# 1-Schematic_8_Bit_Computer_-_Through_Hol.net
KiCad netlist of a schematic drawn in EasyEDA
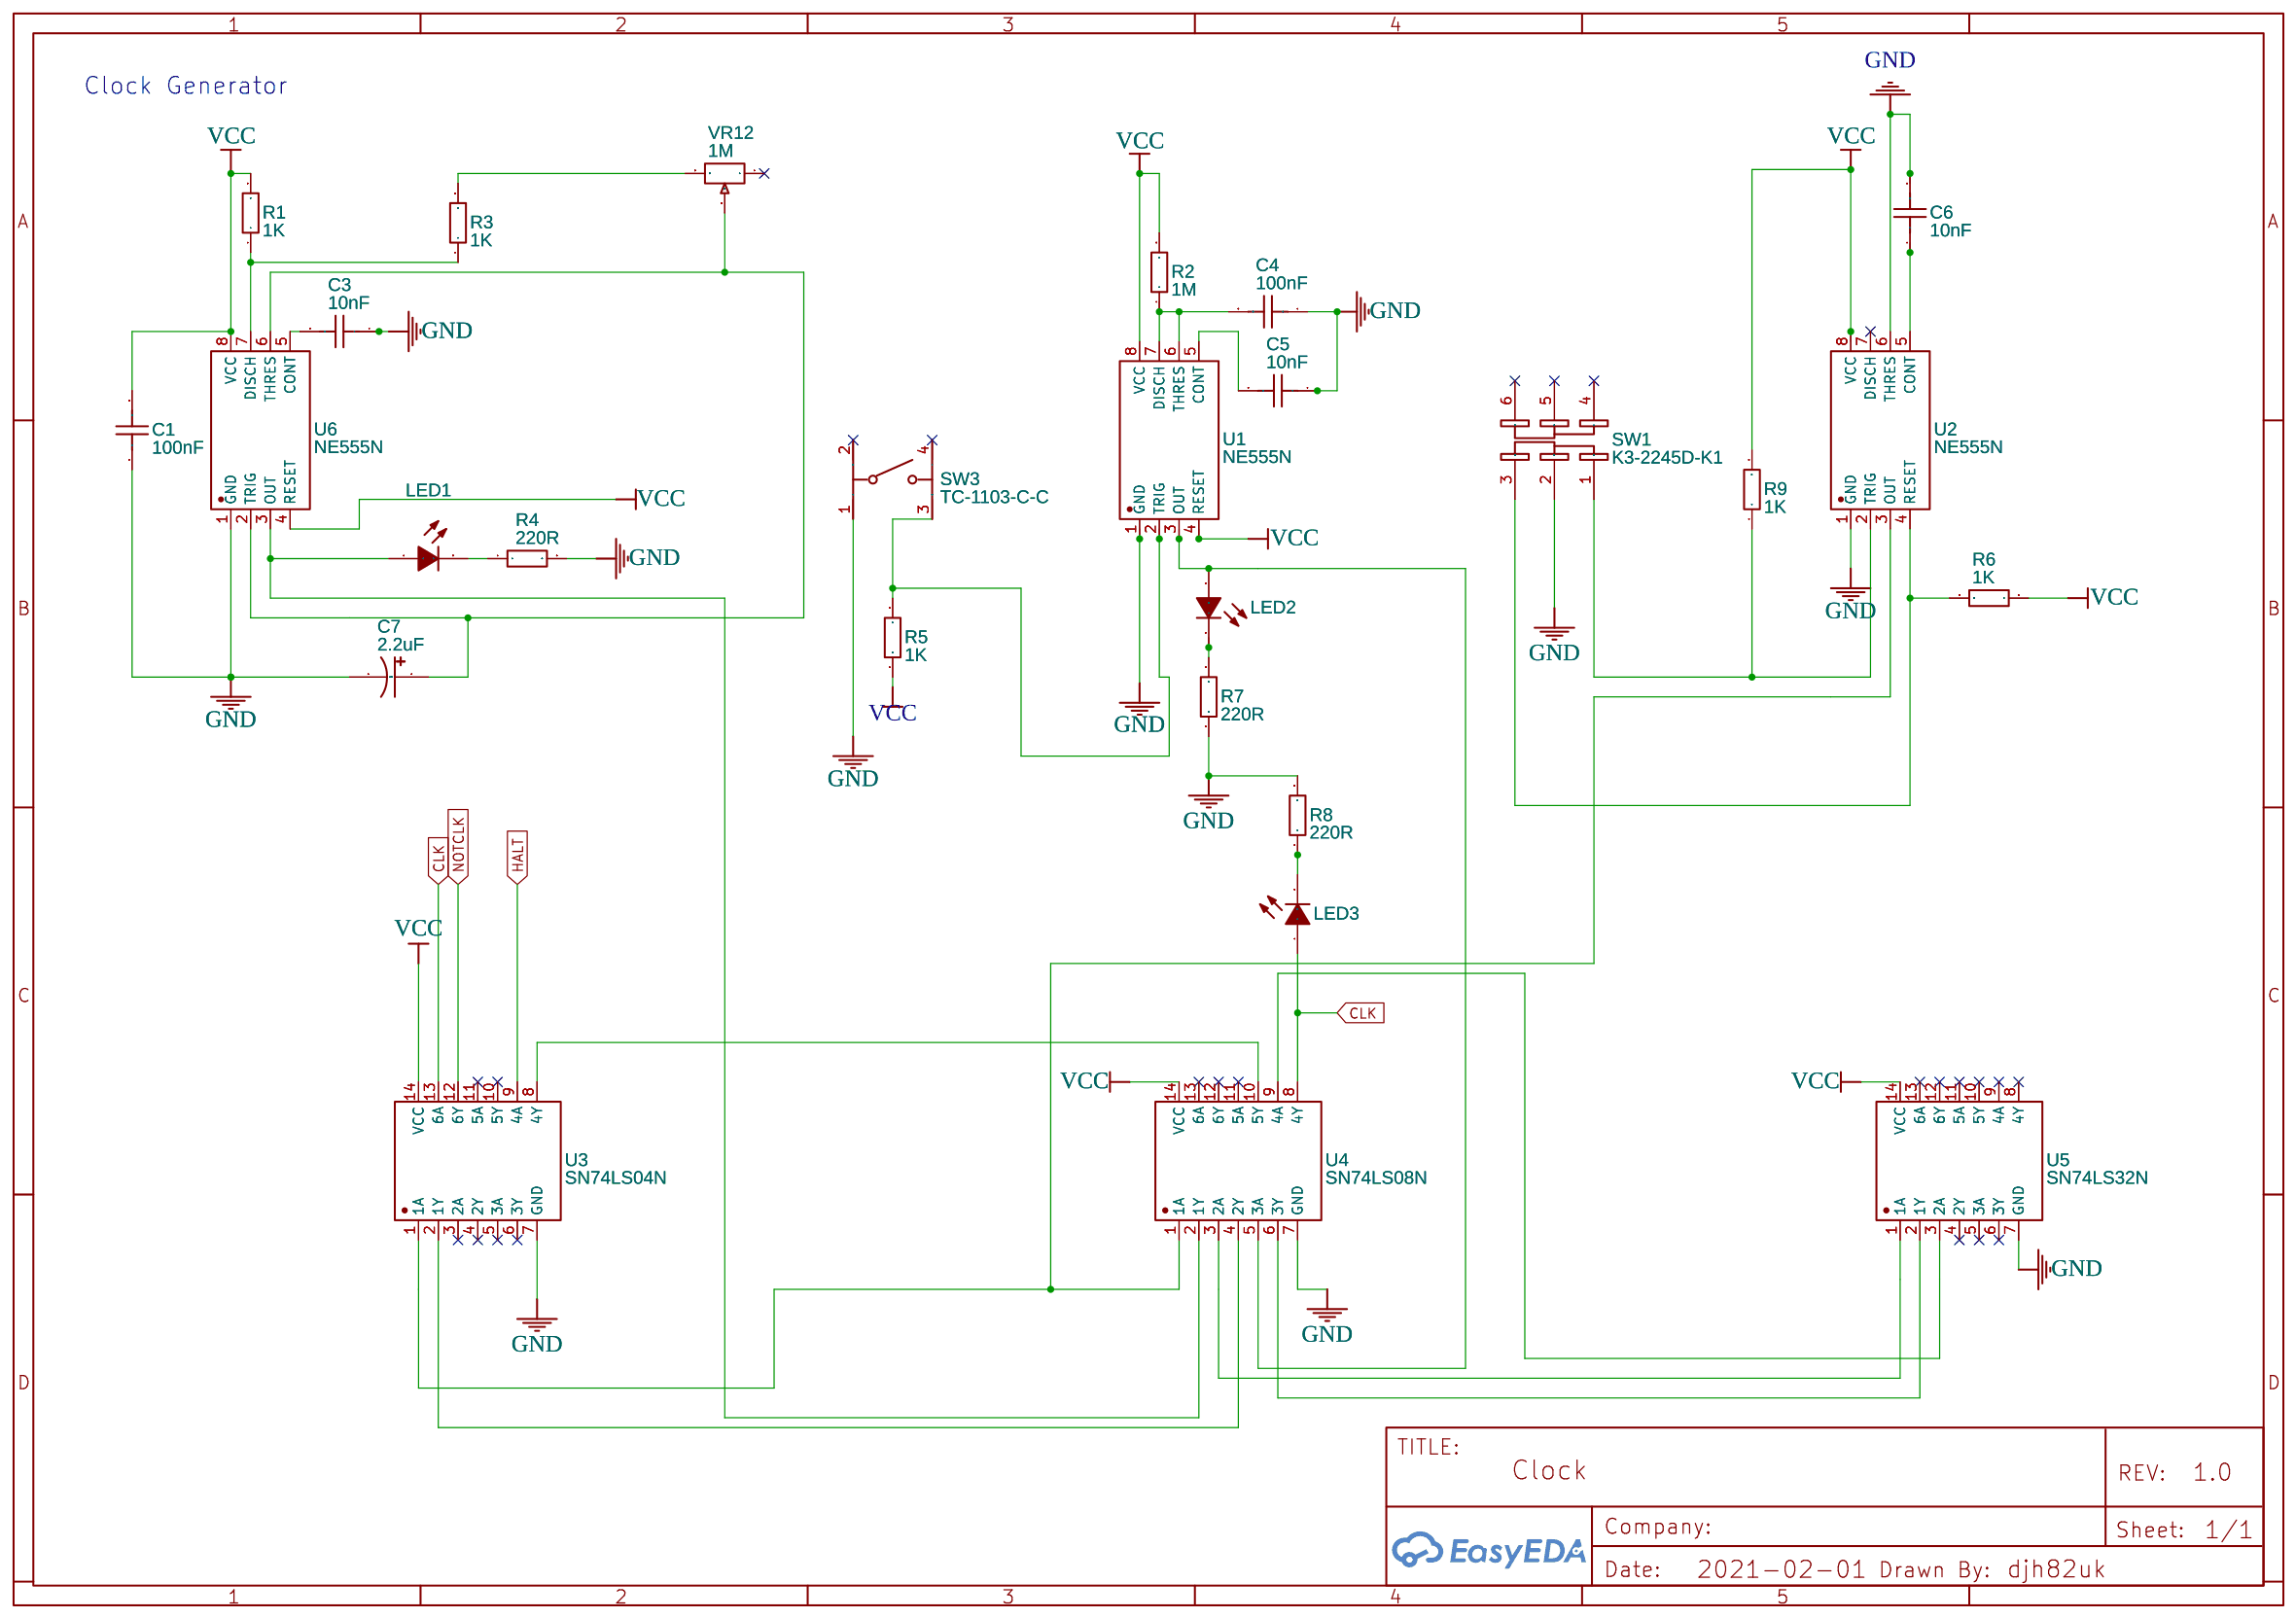
[diagram p0: Clock Circuit]
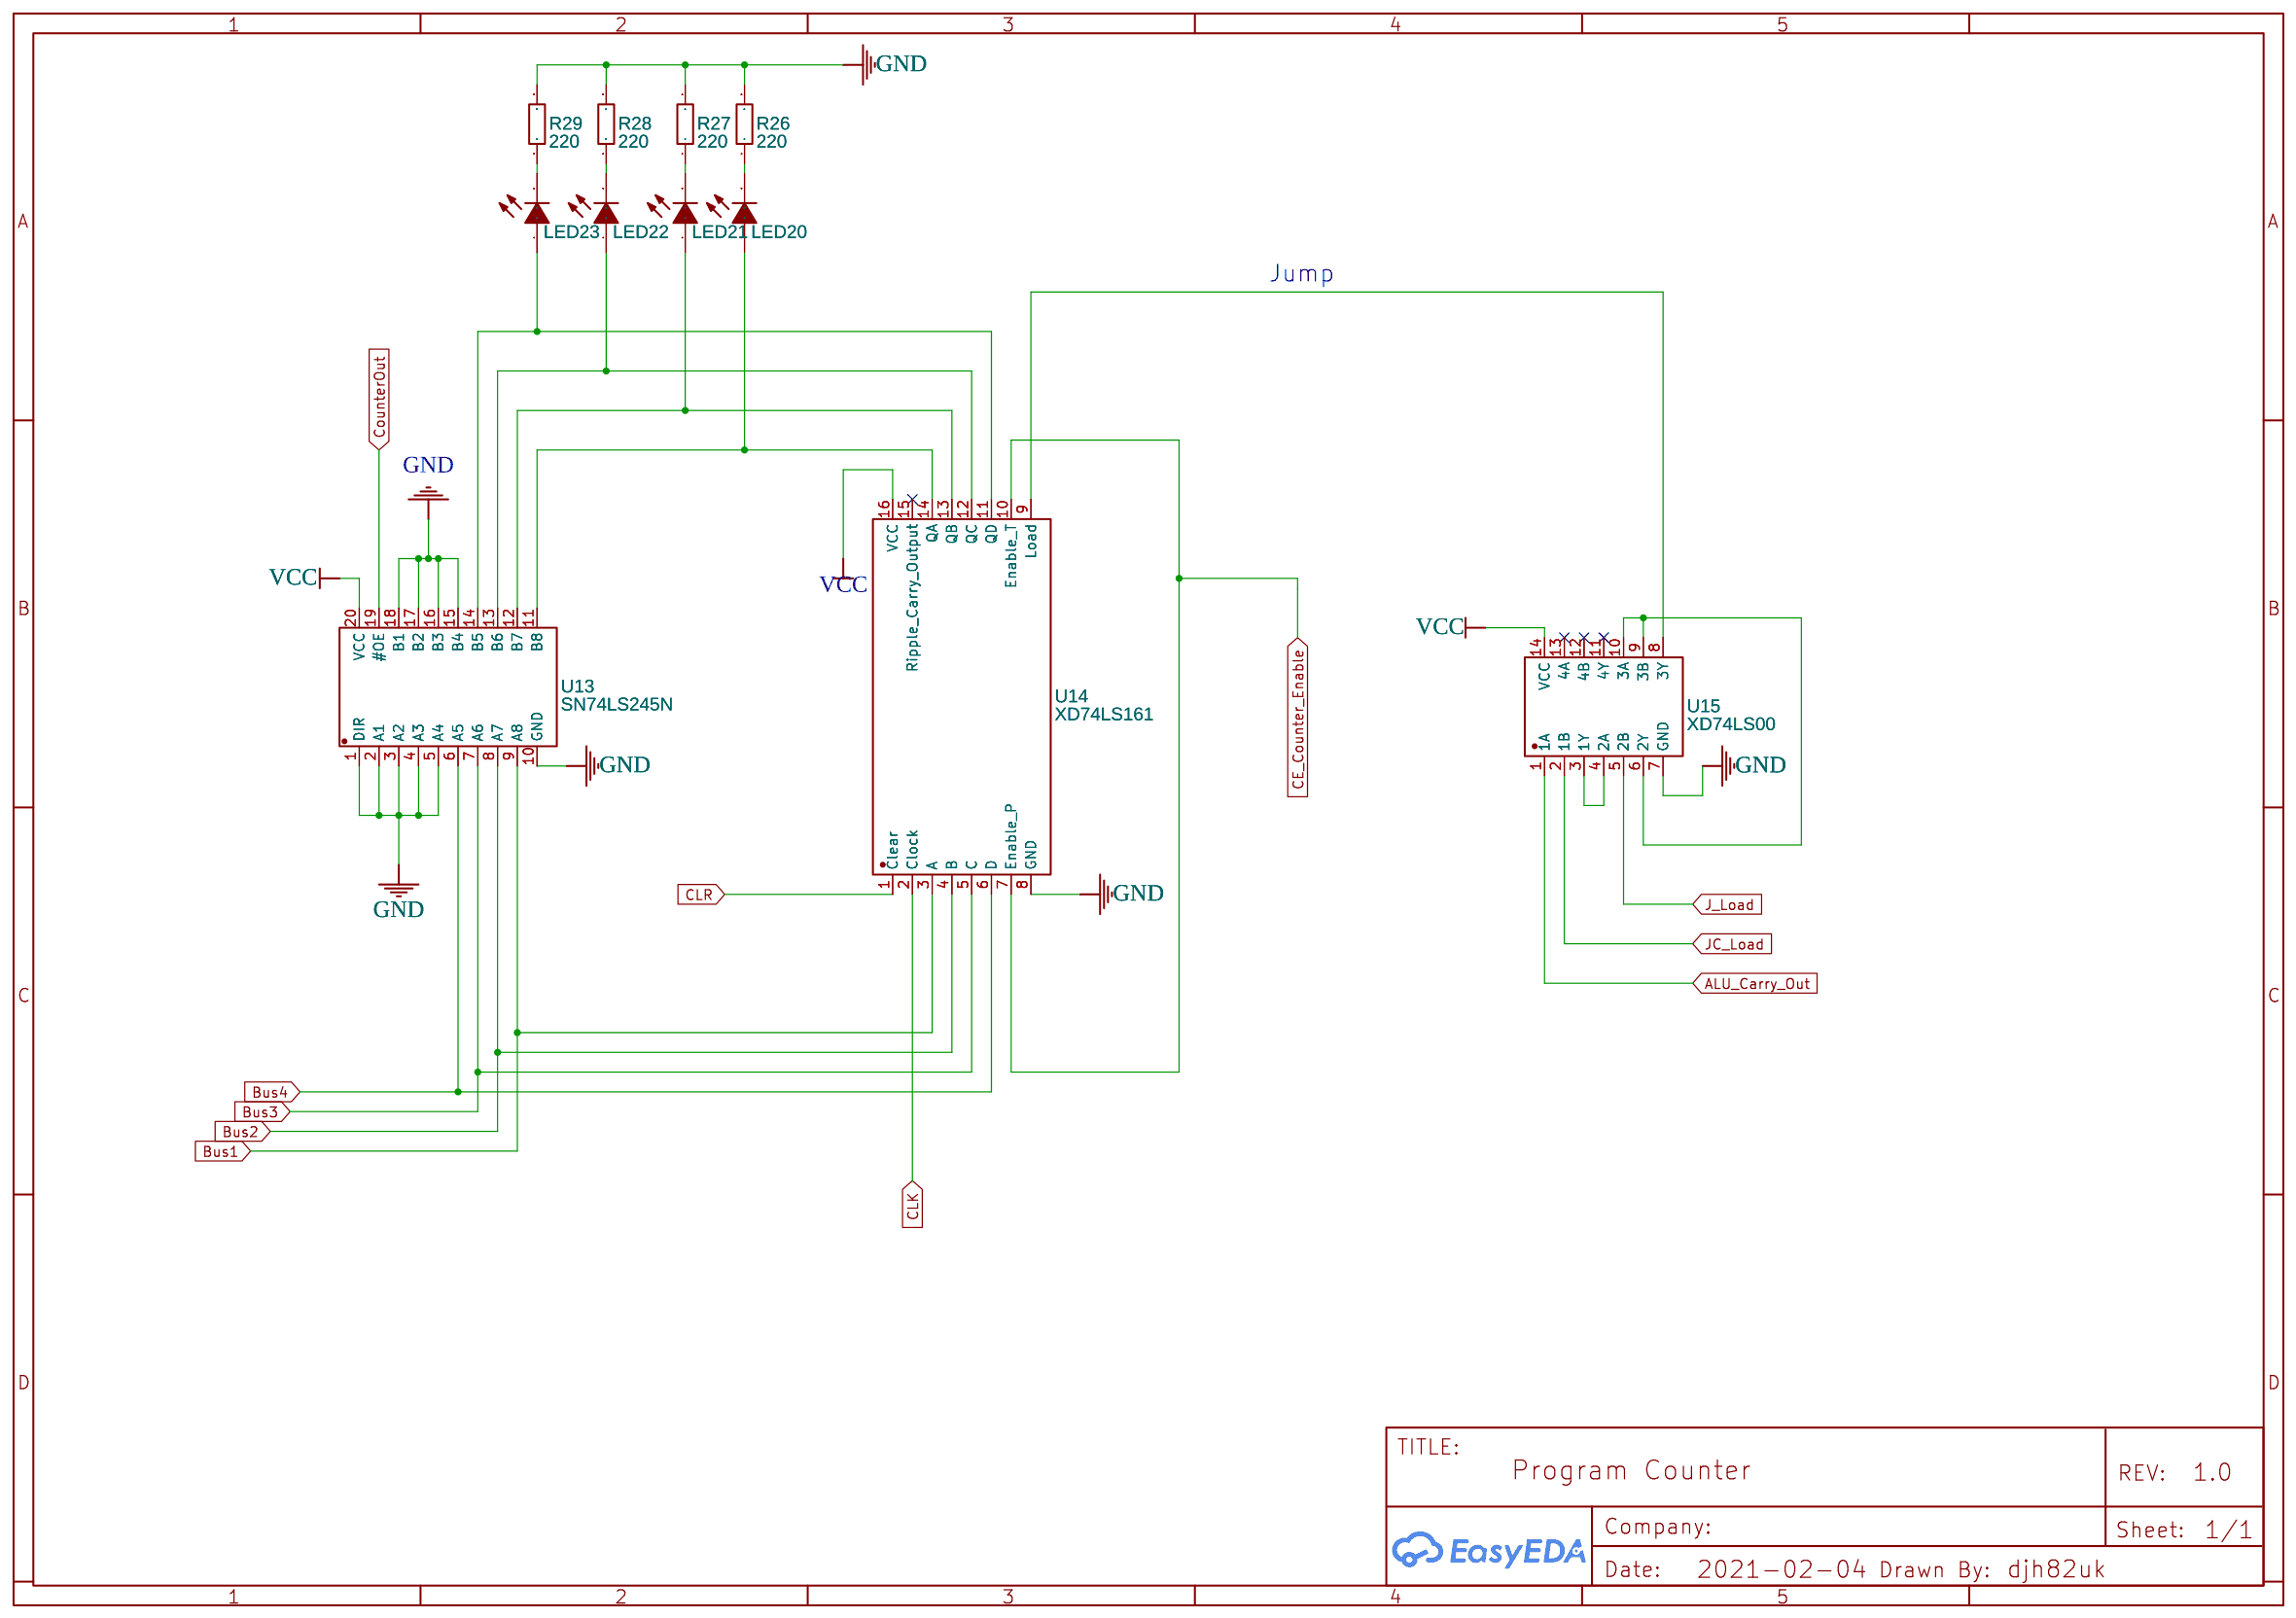
[diagram p1: Program Counter]
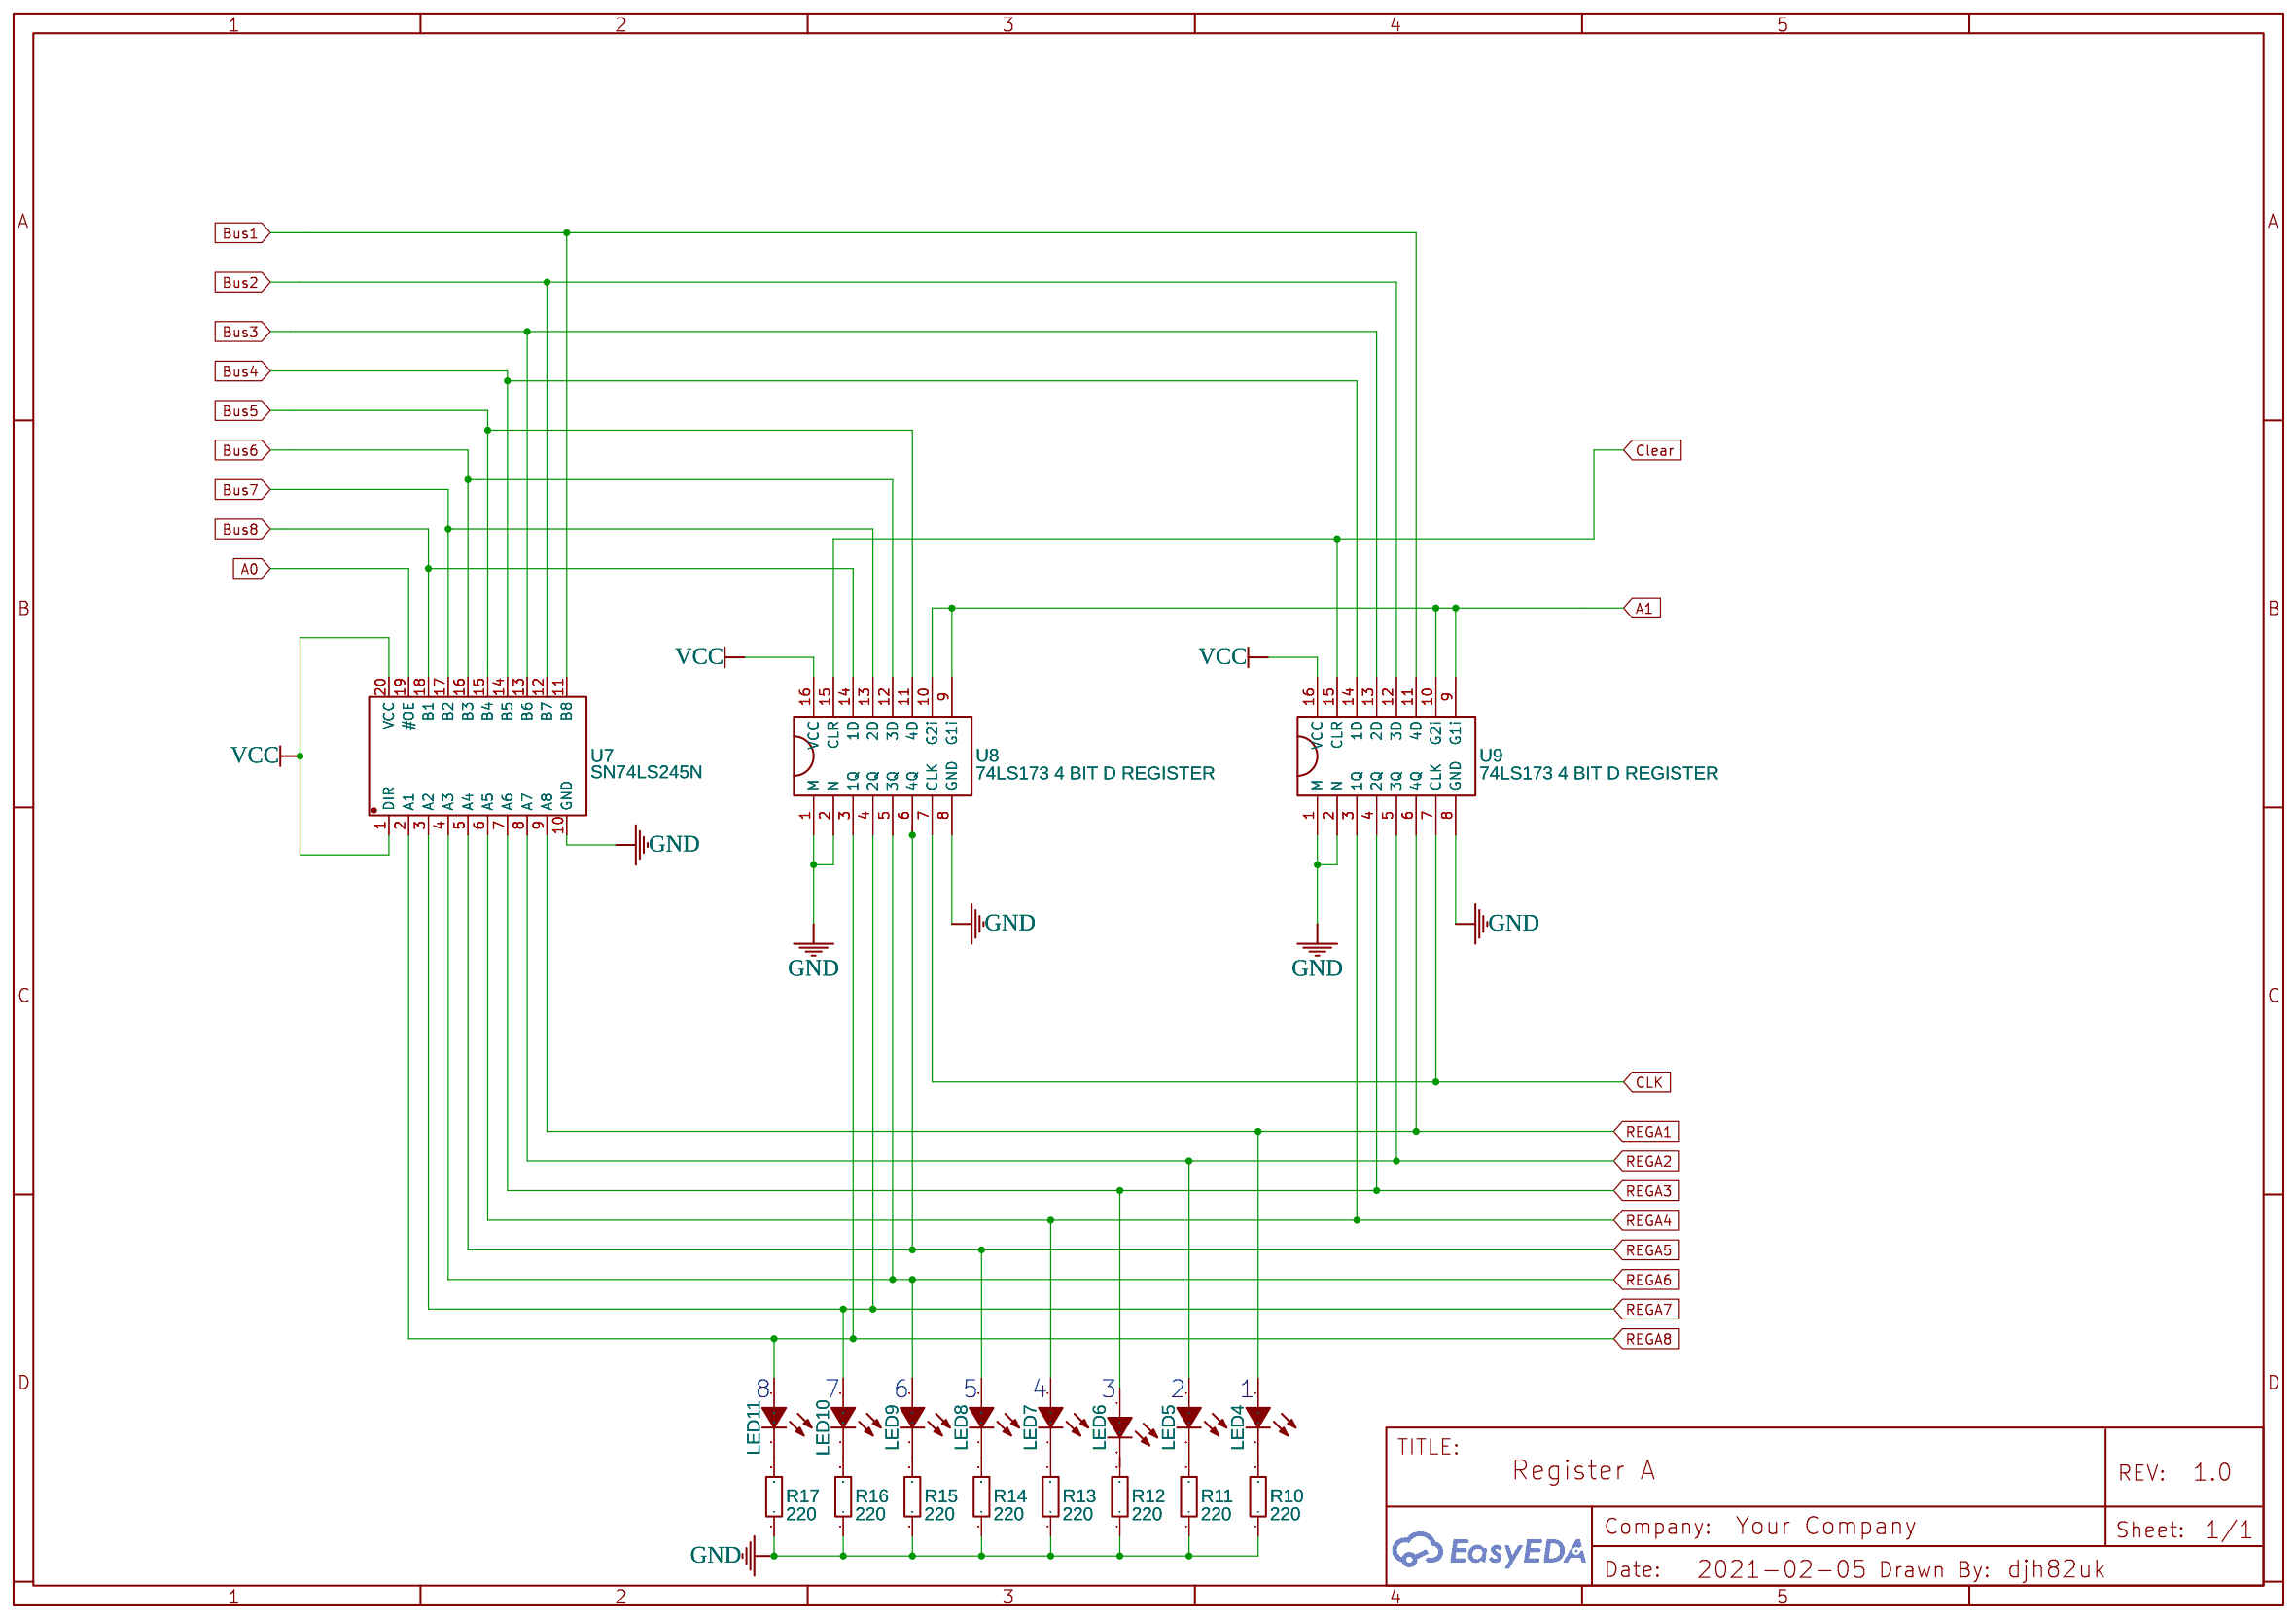
[diagram p2: Register A]
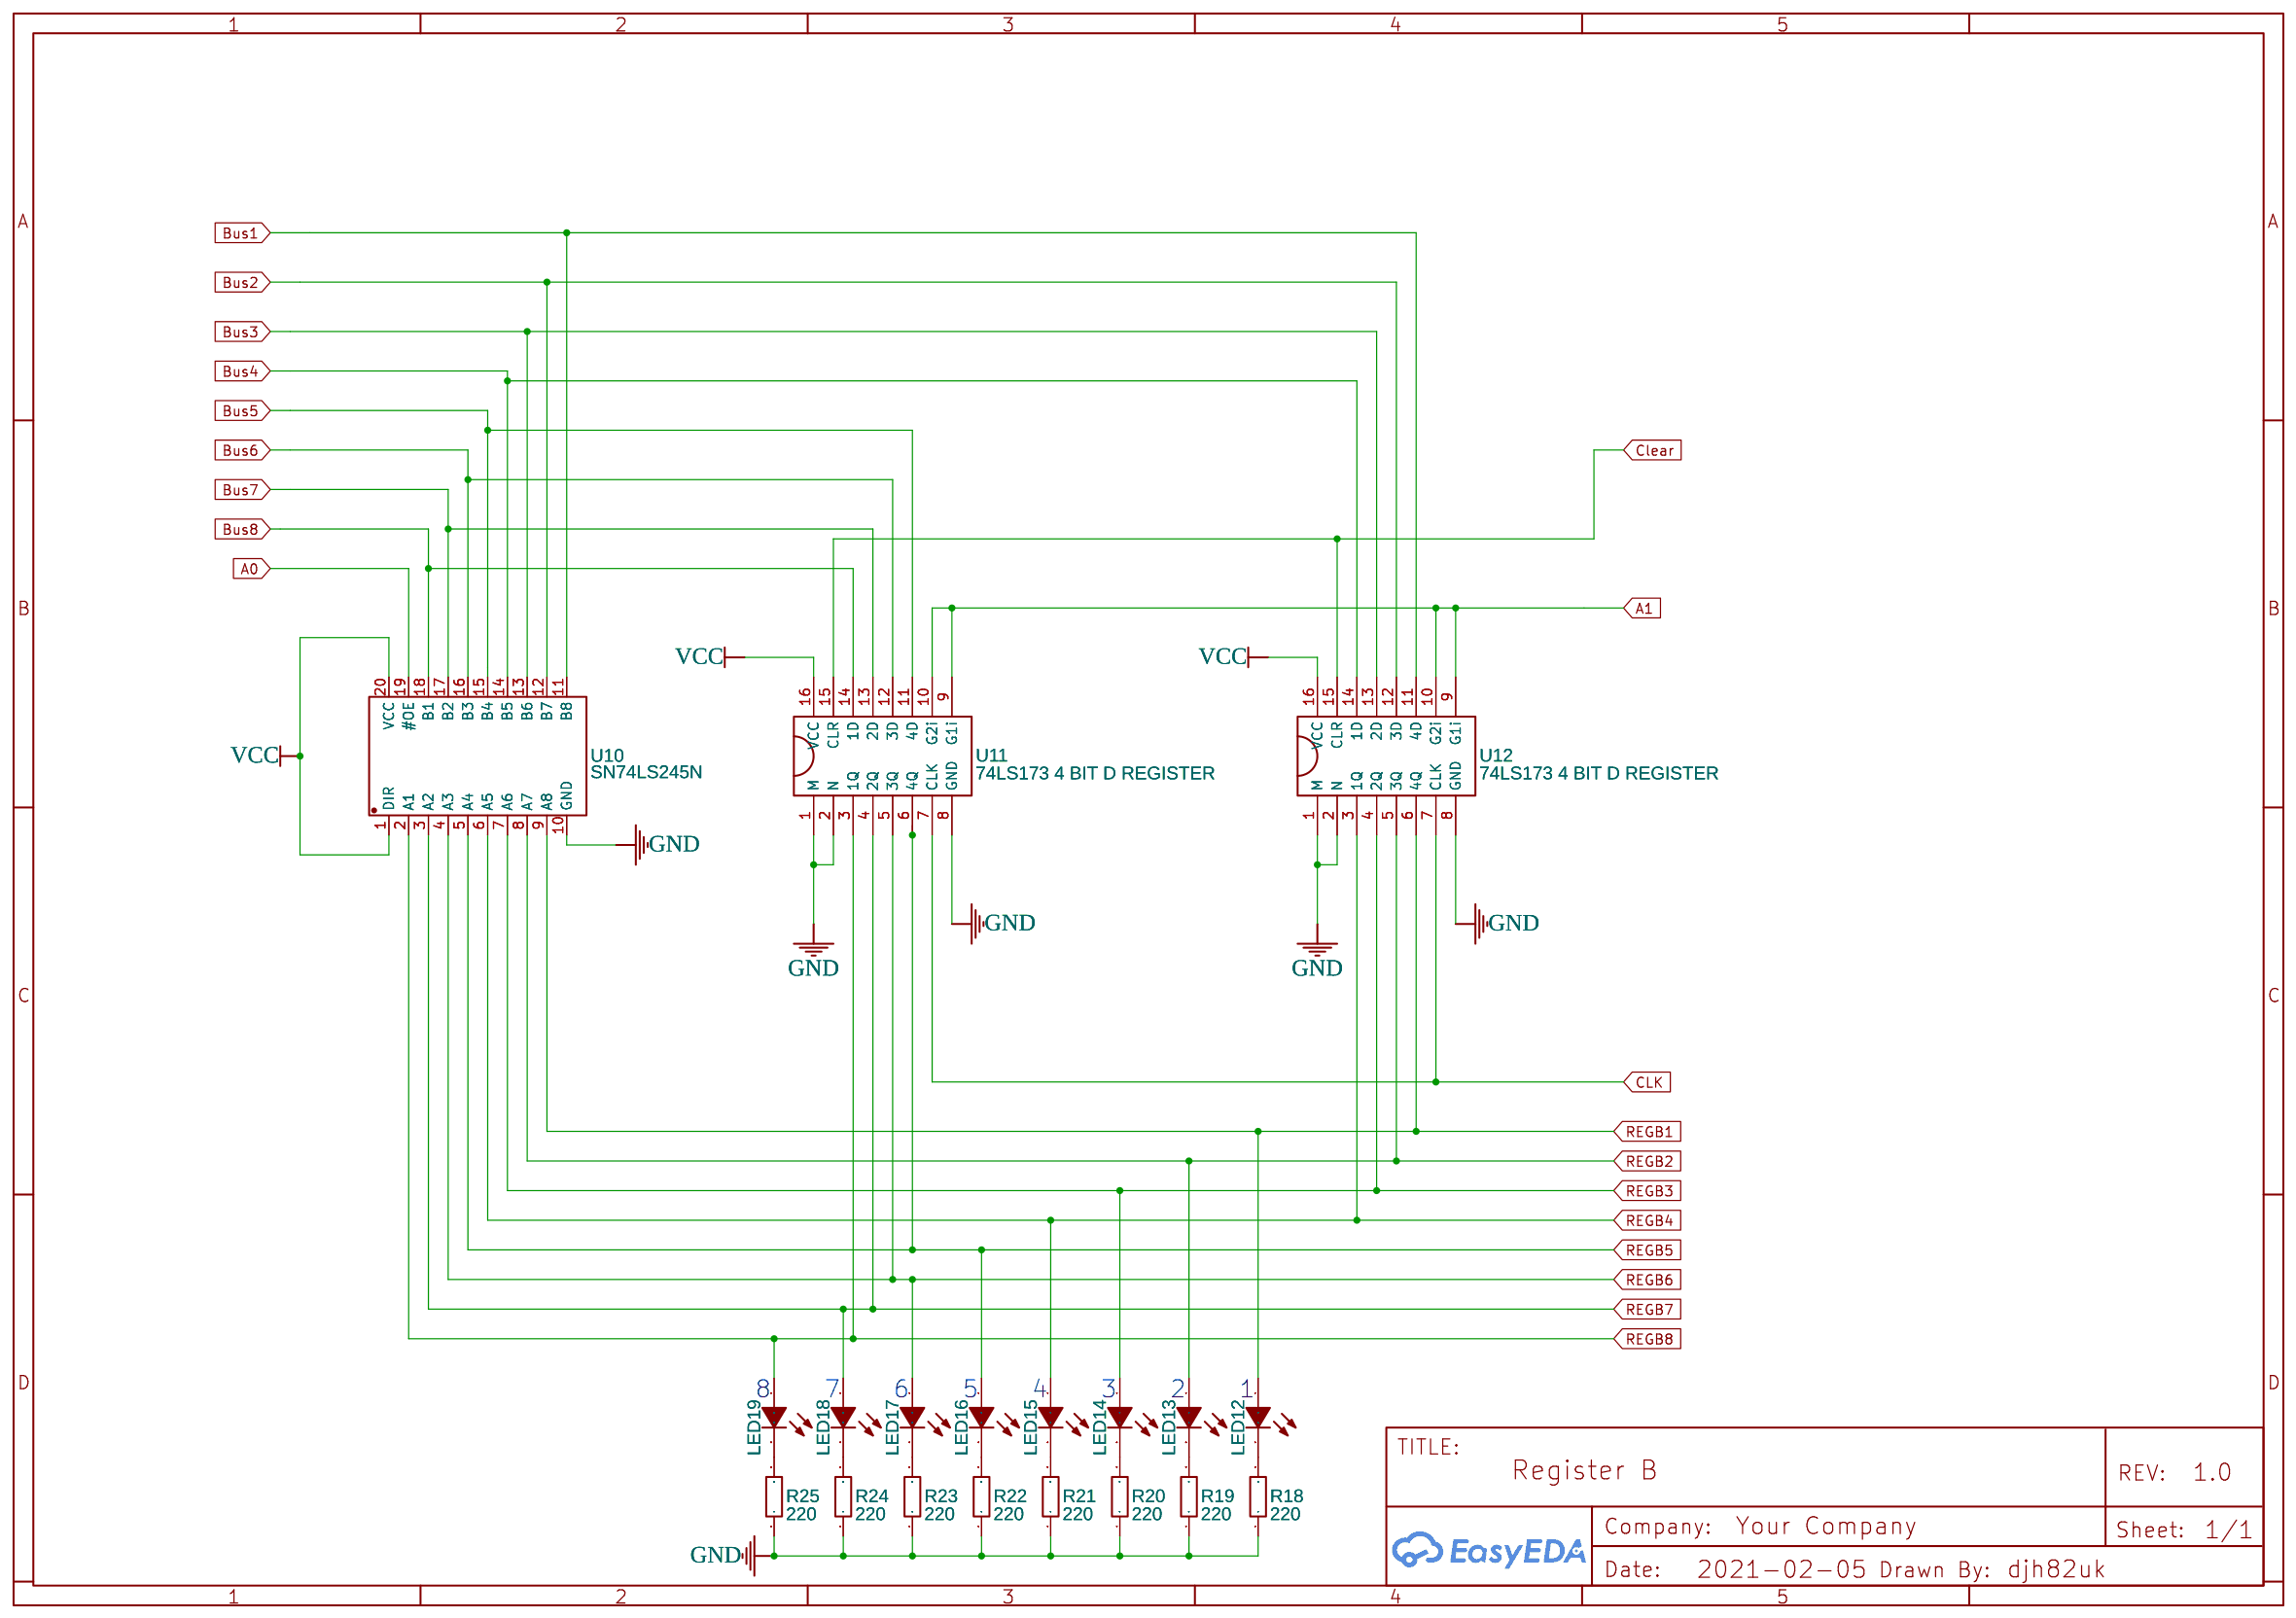
[diagram p3: Register B]
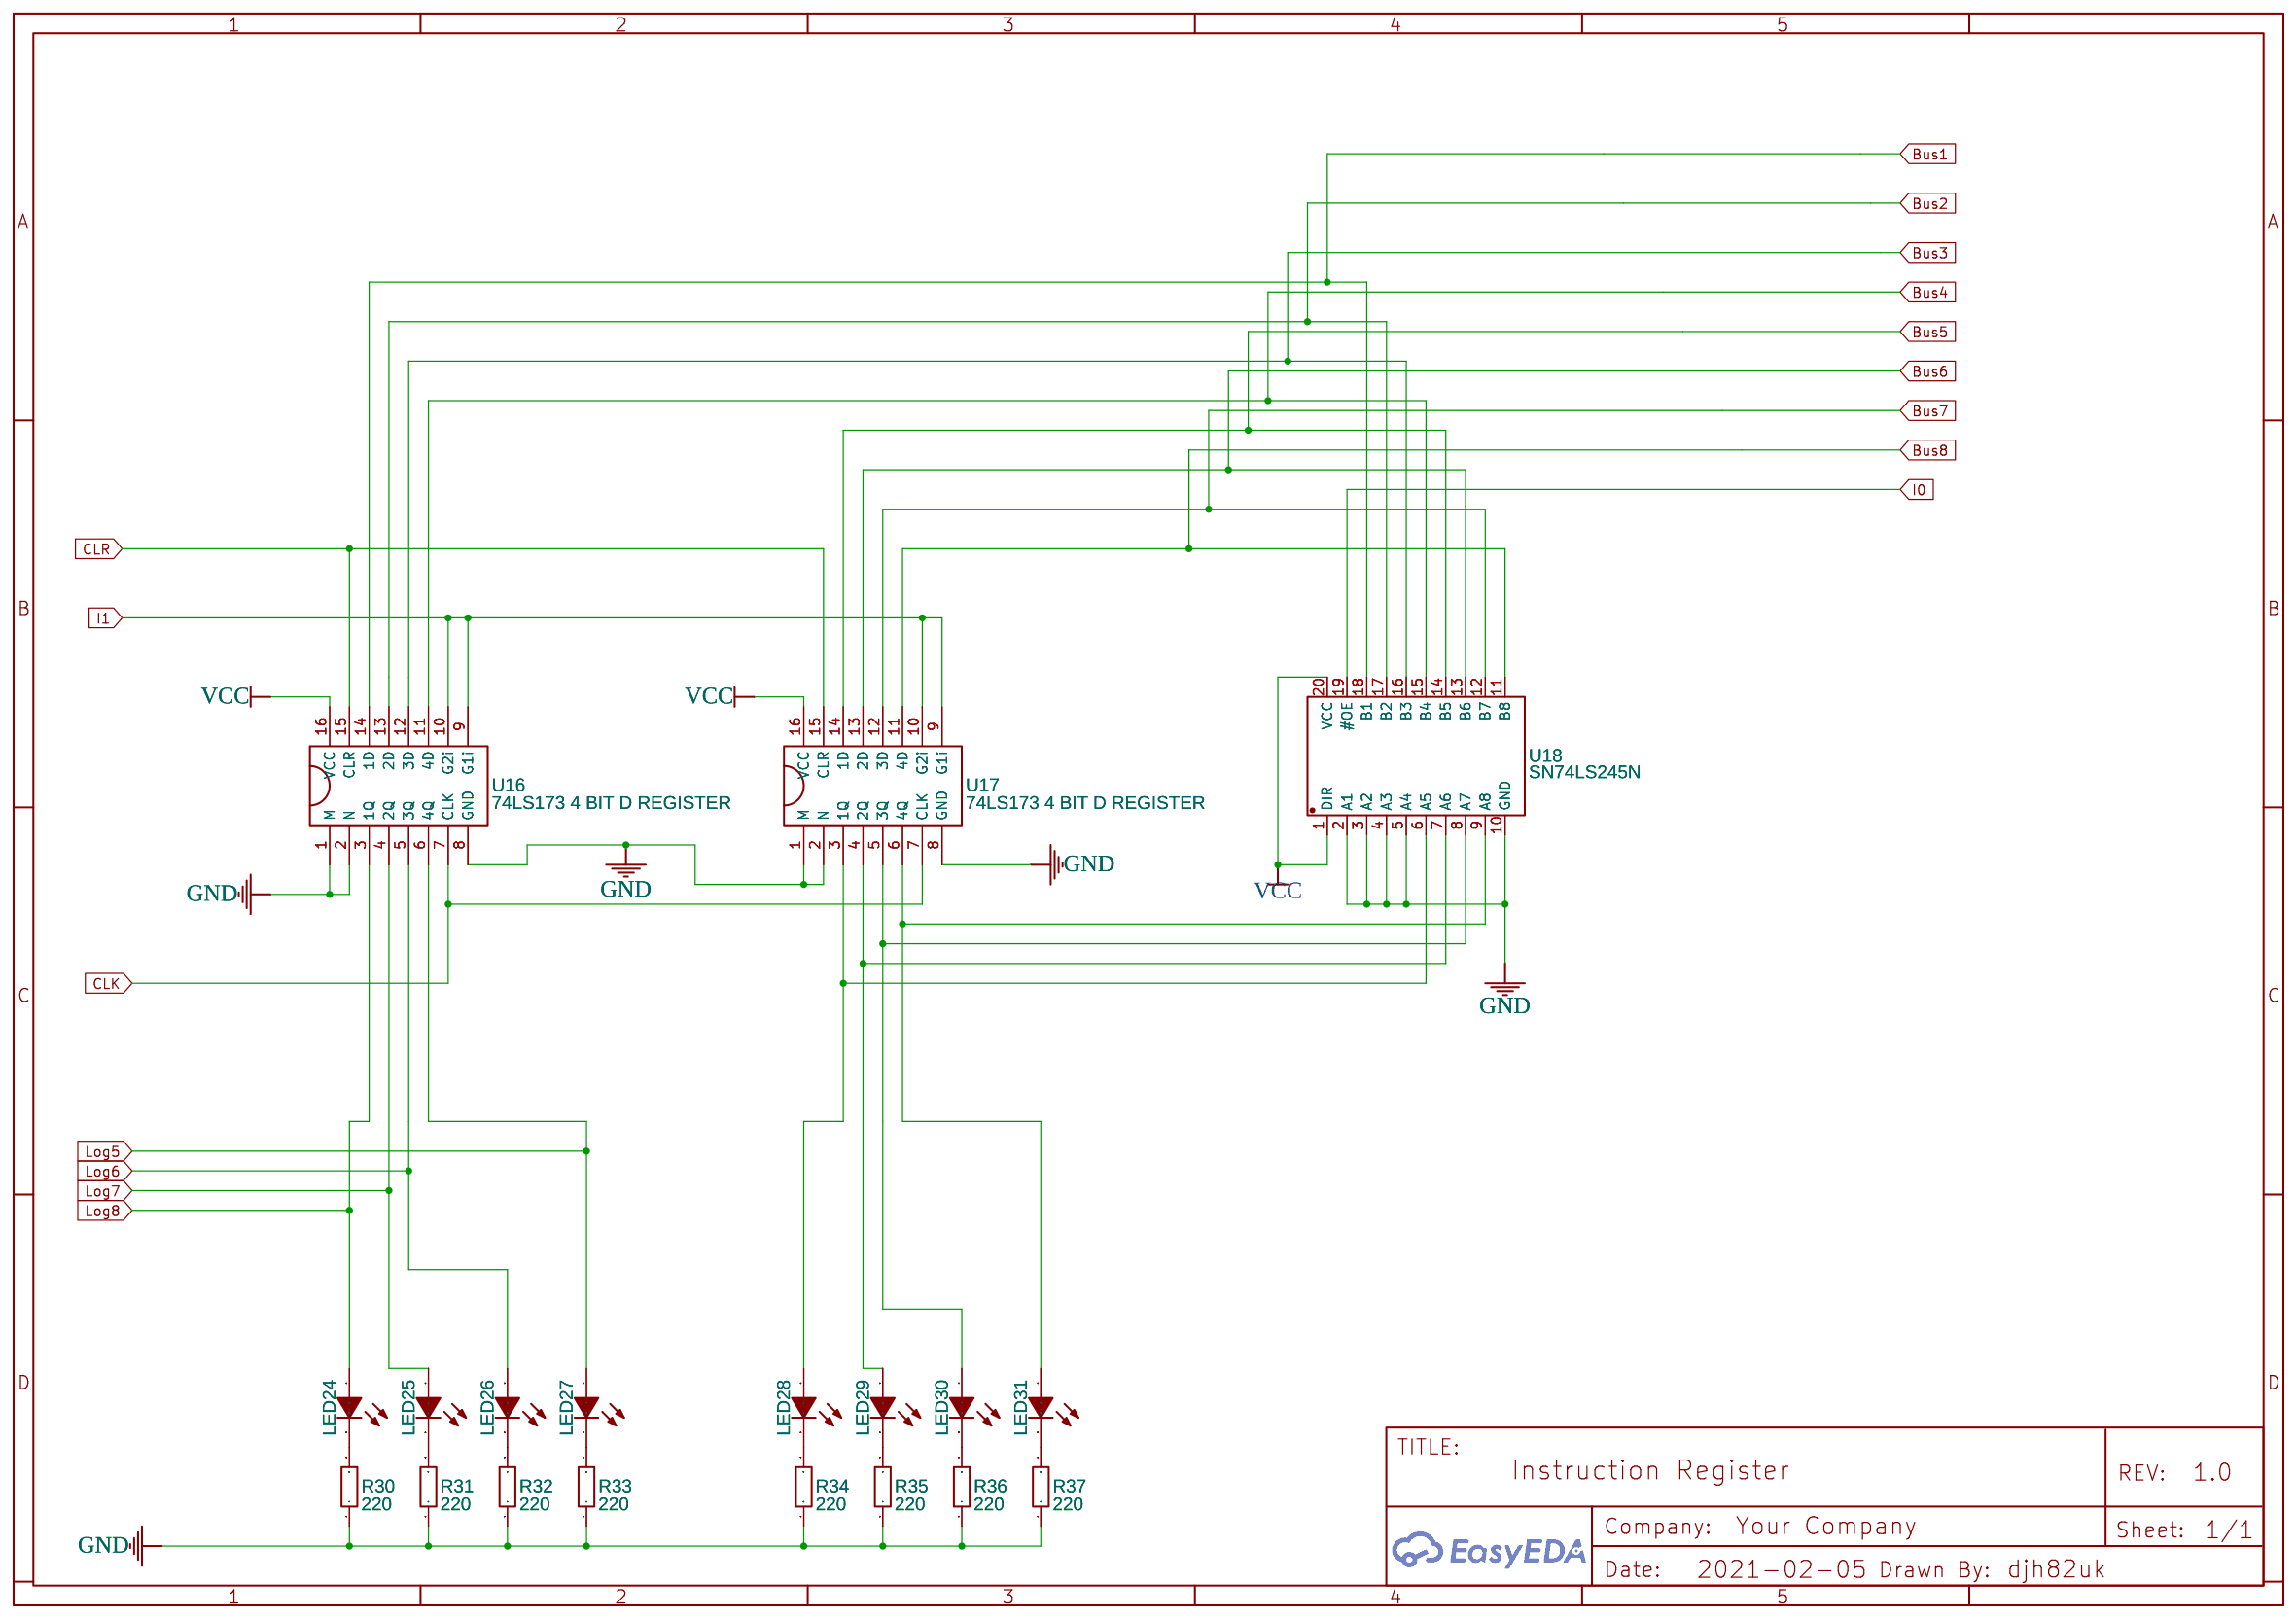
[diagram p4: Instruction Register]
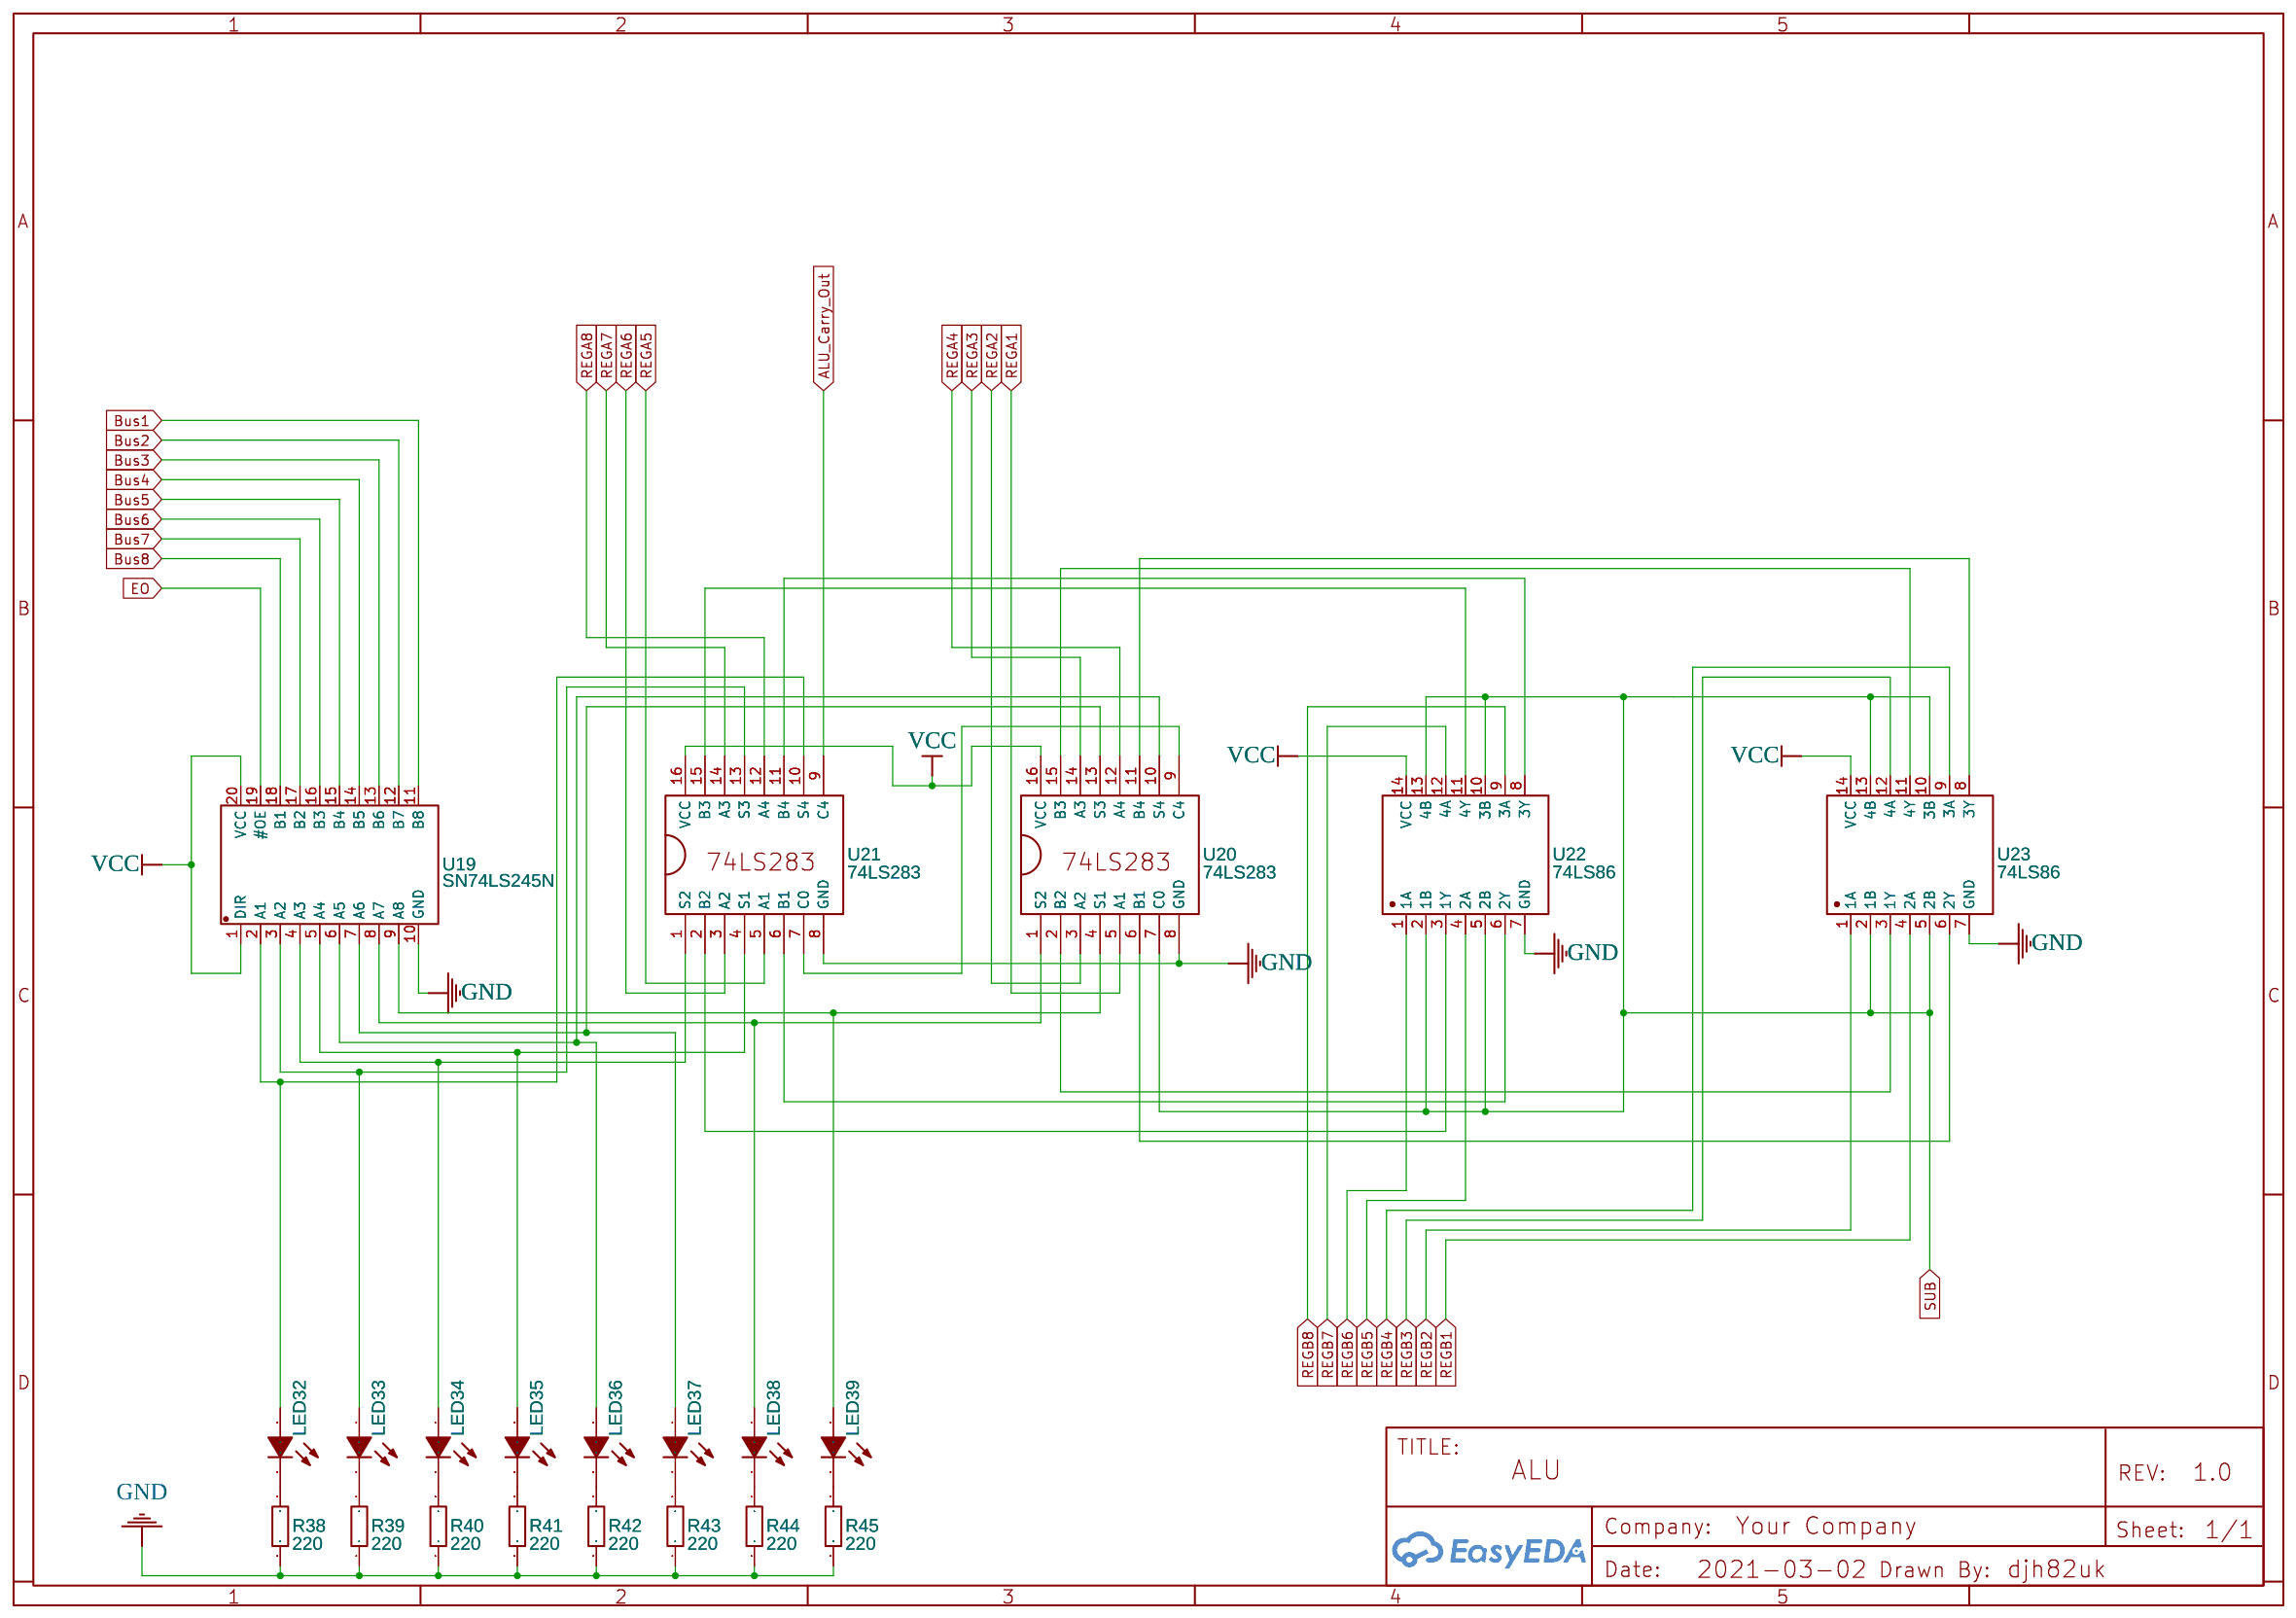
[diagram p5: ALU]
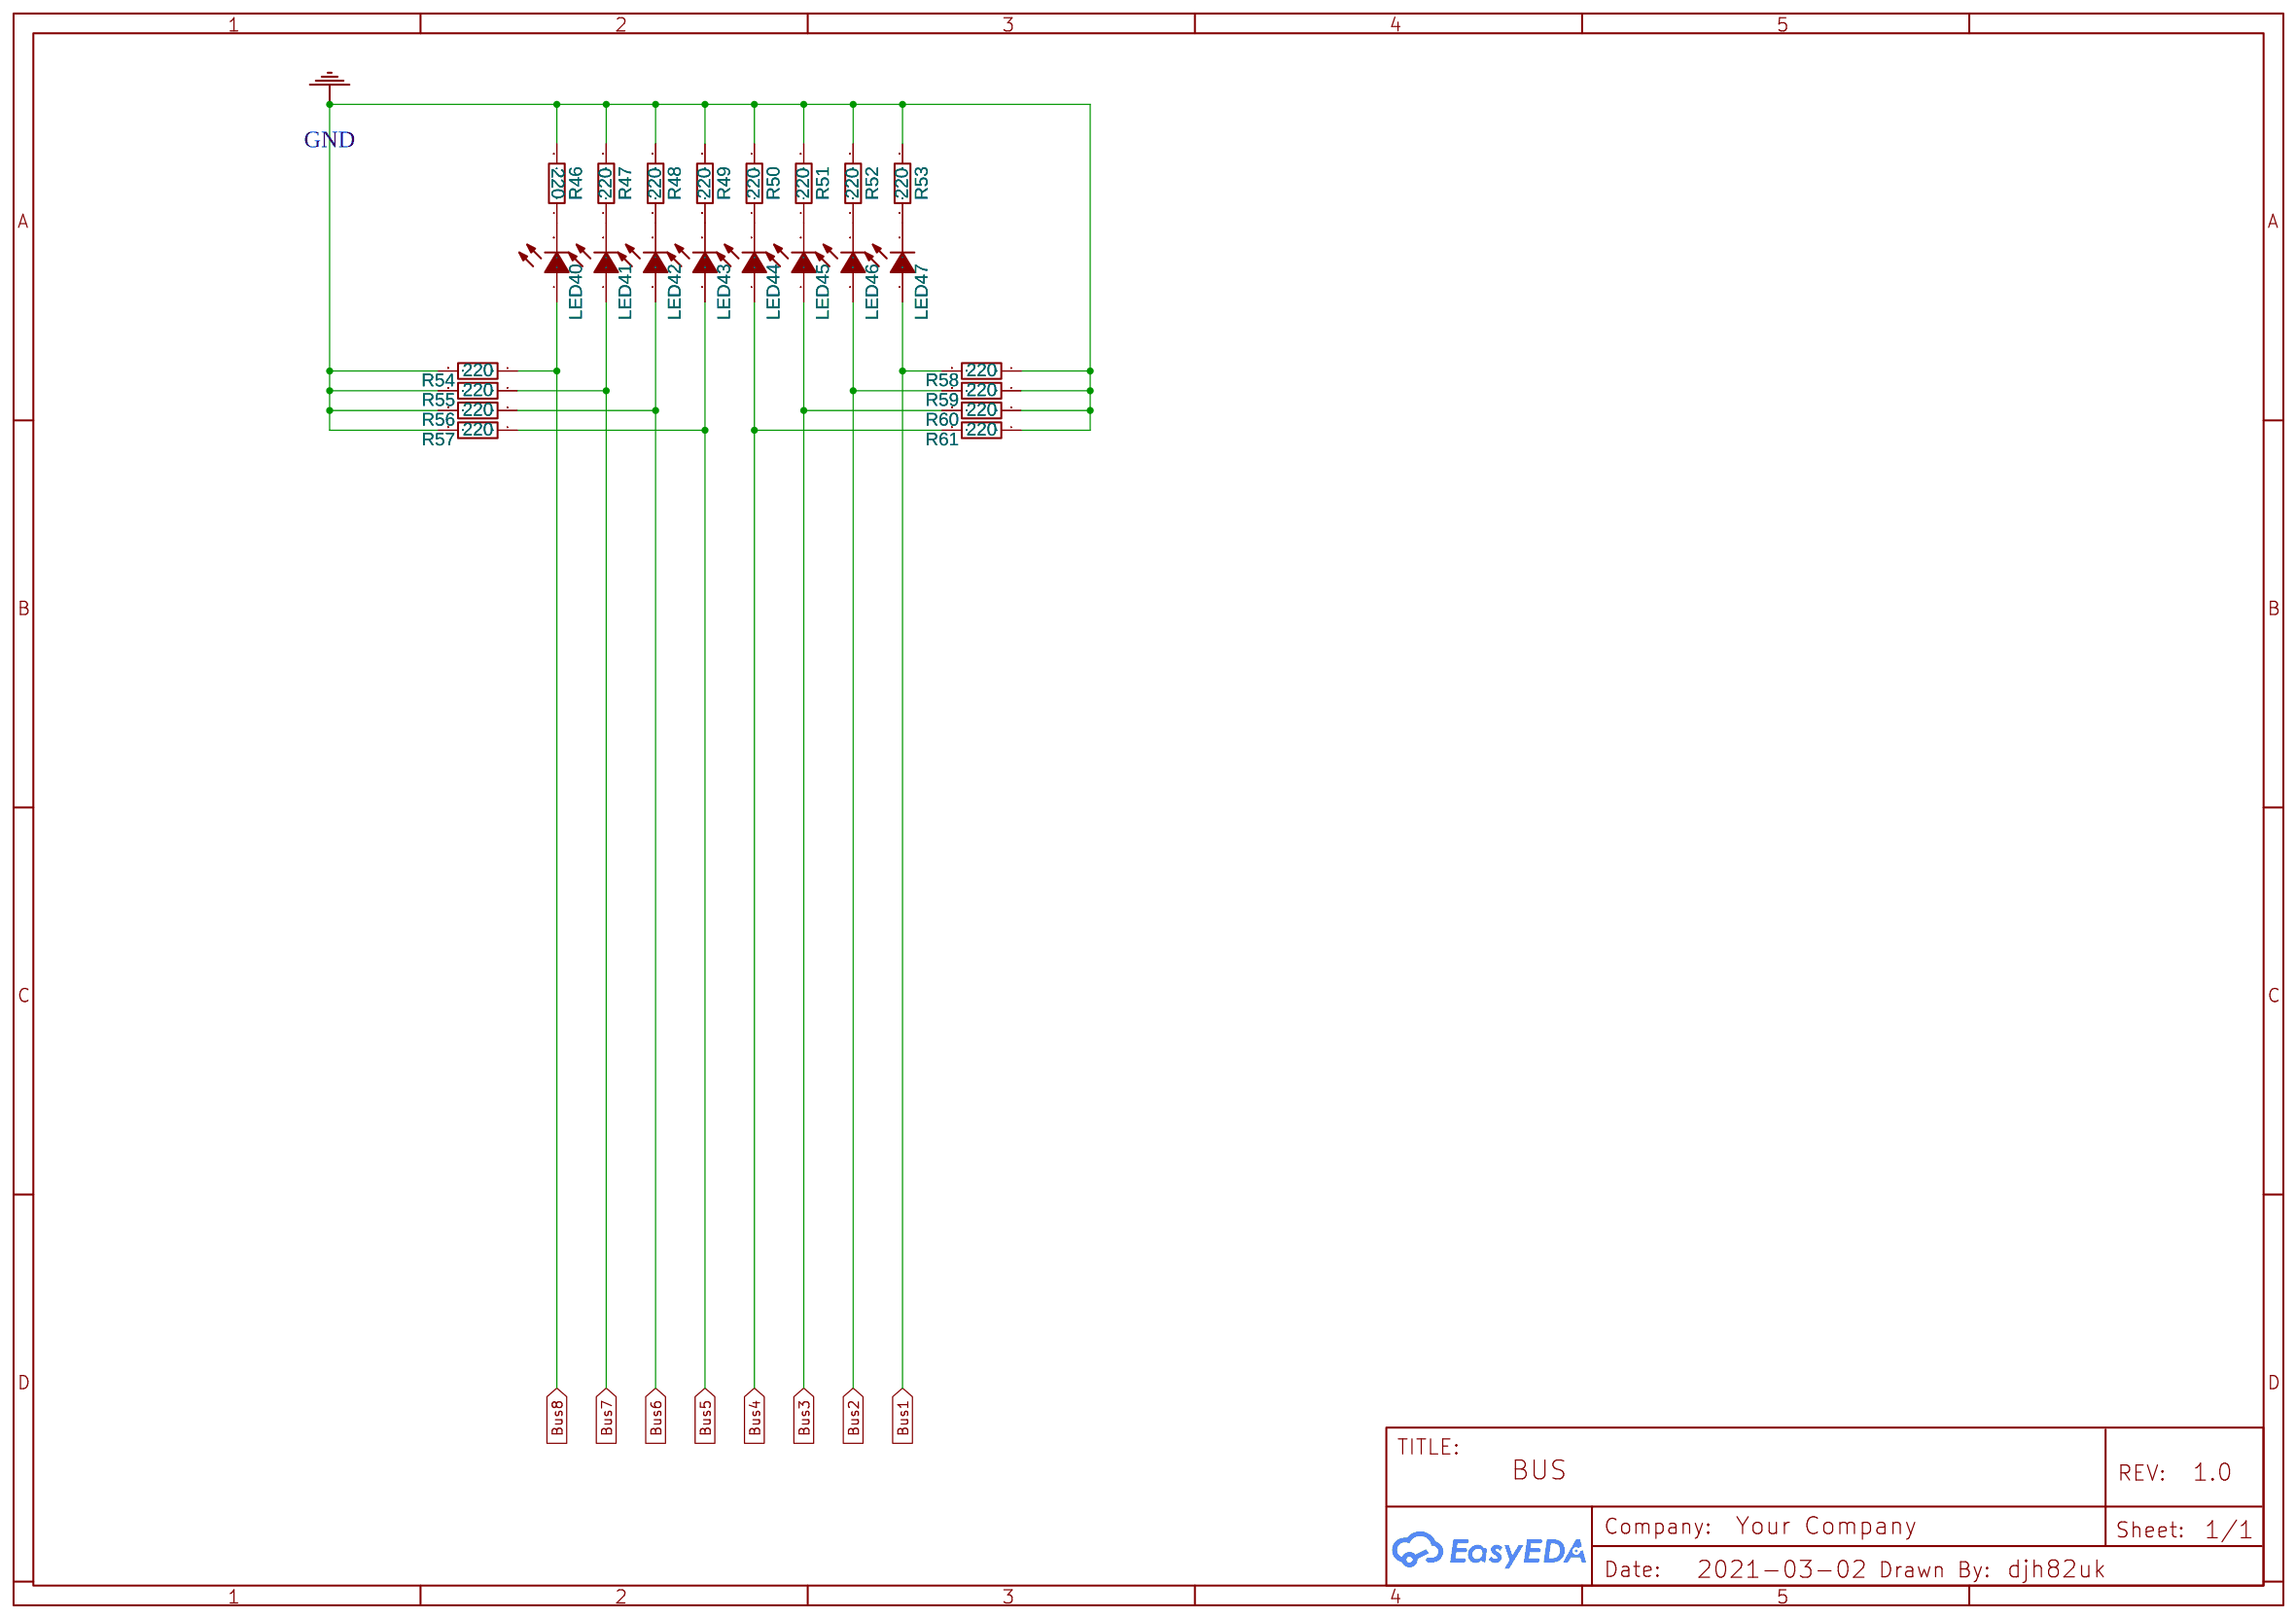
[diagram p6: BUS]

(export (version "E")
  (design (tool "Eeschema 10.0.6"))
  (components
    (comp (ref "C1")
      (value "100nF")
      (fields
        (field (name "BOM_Manufacturer Part") "CC1H103ZC4PD3F4D30MF")
        (field (name "BOM_Supplier Part") "C254066")
      )
      (libsource (lib "") (part "CC1H103ZC4PD3F4D30MF"))
    )
    (comp (ref "C3")
      (value "10nF")
      (fields
        (field (name "BOM_Manufacturer Part") "CC1H103ZC4PD3F4D30MF")
        (field (name "BOM_Supplier Part") "C254066")
      )
      (libsource (lib "") (part "CC1H103ZC4PD3F4D30MF_1"))
    )
    (comp (ref "C4")
      (value "100nF")
      (fields
        (field (name "BOM_Manufacturer Part") "CC1H103ZC4PD3F4D30MF")
        (field (name "BOM_Supplier Part") "C254066")
      )
      (libsource (lib "") (part "CC1H103ZC4PD3F4D30MF_1"))
    )
    (comp (ref "C5")
      (value "10nF")
      (fields
        (field (name "BOM_Manufacturer Part") "CC1H103ZC4PD3F4D30MF")
        (field (name "BOM_Supplier Part") "C254066")
      )
      (libsource (lib "") (part "CC1H103ZC4PD3F4D30MF_1"))
    )
    (comp (ref "C6")
      (value "10nF")
      (fields
        (field (name "BOM_Manufacturer Part") "CC1H103ZC4PD3F4D30MF")
        (field (name "BOM_Supplier Part") "C254066")
      )
      (libsource (lib "") (part "CC1H103ZC4PD3F4D30MF"))
    )
    (comp (ref "C7")
      (value "2.2uF")
      (fields
        (field (name "BOM_Manufacturer Part") "RGA2R2M1HSA-0511G")
        (field (name "BOM_Supplier Part") "C358629")
      )
      (libsource (lib "") (part "RGA2R2M1HSA-0511G"))
    )
    (comp (ref "LED1")
      (value "333-2SYGD/S530-E2-L")
      (fields (field (name "BOM_Supplier Part") "C99697"))
      (libsource (lib "") (part "333-2SYGD/S530-E2-L"))
    )
    (comp (ref "LED2")
      (value "333-2SYGD/S530-E2-L")
      (fields (field (name "BOM_Supplier Part") "C99697"))
      (libsource (lib "") (part "333-2SYGD/S530-E2-L_2"))
    )
    (comp (ref "LED3")
      (value "333-2SYGD/S530-E2-L")
      (fields (field (name "BOM_Supplier Part") "C99697"))
      (libsource (lib "") (part "333-2SYGD/S530-E2-L_1"))
    )
    (comp (ref "R1")
      (value "1K")
      (fields
        (field (name "BOM_Manufacturer Part") "MFR0W4F1003A50")
        (field (name "BOM_Supplier Part") "C58597")
      )
      (libsource (lib "") (part "MFR0W4F1003A50_1"))
    )
    (comp (ref "R2")
      (value "1M")
      (fields
        (field (name "BOM_Manufacturer Part") "MFR0W4F1003A50")
        (field (name "BOM_Supplier Part") "C58597")
      )
      (libsource (lib "") (part "MFR0W4F1003A50_1"))
    )
    (comp (ref "R3")
      (value "1K")
      (fields
        (field (name "BOM_Manufacturer Part") "MFR0W4F1003A50")
        (field (name "BOM_Supplier Part") "C58597")
      )
      (libsource (lib "") (part "MFR0W4F1003A50_1"))
    )
    (comp (ref "R4")
      (value "220R")
      (fields
        (field (name "BOM_Manufacturer Part") "MFR0W4F1003A50")
        (field (name "BOM_Supplier Part") "C58597")
      )
      (libsource (lib "") (part "MFR0W4F1003A50_2"))
    )
    (comp (ref "R5")
      (value "1K")
      (fields
        (field (name "BOM_Manufacturer Part") "MFR0W4F1003A50")
        (field (name "BOM_Supplier Part") "C58597")
      )
      (libsource (lib "") (part "MFR0W4F1003A50_1"))
    )
    (comp (ref "R6")
      (value "1K")
      (fields
        (field (name "BOM_Manufacturer Part") "MFR0W4F1003A50")
        (field (name "BOM_Supplier Part") "C58597")
      )
      (libsource (lib "") (part "MFR0W4F1003A50"))
    )
    (comp (ref "R7")
      (value "220R")
      (fields
        (field (name "BOM_Manufacturer Part") "MFR0W4F1003A50")
        (field (name "BOM_Supplier Part") "C58597")
      )
      (libsource (lib "") (part "MFR0W4F1003A50_1"))
    )
    (comp (ref "R8")
      (value "220R")
      (fields
        (field (name "BOM_Manufacturer Part") "MFR0W4F1003A50")
        (field (name "BOM_Supplier Part") "C58597")
      )
      (libsource (lib "") (part "MFR0W4F1003A50_1"))
    )
    (comp (ref "R9")
      (value "1K")
      (fields
        (field (name "BOM_Manufacturer Part") "MFR0W4F1003A50")
        (field (name "BOM_Supplier Part") "C58597")
      )
      (libsource (lib "") (part "MFR0W4F1003A50_1"))
    )
    (comp (ref "SW1")
      (value "K3-2245D-K1")
      (fields (field (name "BOM_Supplier Part") "C223864"))
      (libsource (lib "") (part "K3-2245D-K1"))
    )
    (comp (ref "SW3")
      (value "TC-1103-C-C")
      (fields (field (name "BOM_Supplier Part") "C318976"))
      (libsource (lib "") (part "TC-1103-C-C"))
    )
    (comp (ref "U1")
      (value "NE555N")
      (fields (field (name "BOM_Supplier Part") "C398063"))
      (libsource (lib "") (part "NE555N"))
    )
    (comp (ref "U2")
      (value "NE555N")
      (fields (field (name "BOM_Supplier Part") "C398063"))
      (libsource (lib "") (part "NE555N"))
    )
    (comp (ref "U3")
      (value "SN74LS04N")
      (fields (field (name "BOM_Supplier Part") "C183657"))
      (libsource (lib "") (part "SN74LS04N"))
    )
    (comp (ref "U4")
      (value "SN74LS08N")
      (fields (field (name "BOM_Manufacturer Part") "SN74LS04N") (field (name "BOM_Supplier Part") "C183657"))
      (libsource (lib "") (part "SN74LS04N"))
    )
    (comp (ref "U5")
      (value "SN74LS32N")
      (fields (field (name "BOM_Manufacturer Part") "SN74LS04N") (field (name "BOM_Supplier Part") "C183657"))
      (libsource (lib "") (part "SN74LS04N"))
    )
    (comp (ref "U6")
      (value "NE555N")
      (fields (field (name "BOM_Supplier Part") "C398063"))
      (libsource (lib "") (part "NE555N"))
    )
    (comp (ref "VR12")
      (value "1M")
      (fields
        (field (name "BOM_Manufacturer Part") "3296W-1-104")
        (field (name "BOM_Supplier Part") "C118963")
      )
      (libsource (lib "") (part "3296W-1-104"))
    )
    (comp (ref "LED20")
      (value "333-2SYGD/S530-E2-L")
      (fields (field (name "BOM_Supplier Part") "C99697"))
      (libsource (lib "") (part "333-2SYGD/S530-E2-L"))
    )
    (comp (ref "LED21")
      (value "333-2SYGD/S530-E2-L")
      (fields (field (name "BOM_Supplier Part") "C99697"))
      (libsource (lib "") (part "333-2SYGD/S530-E2-L"))
    )
    (comp (ref "LED22")
      (value "333-2SYGD/S530-E2-L")
      (fields (field (name "BOM_Supplier Part") "C99697"))
      (libsource (lib "") (part "333-2SYGD/S530-E2-L"))
    )
    (comp (ref "LED23")
      (value "333-2SYGD/S530-E2-L")
      (fields (field (name "BOM_Supplier Part") "C99697"))
      (libsource (lib "") (part "333-2SYGD/S530-E2-L"))
    )
    (comp (ref "R26")
      (value "220")
      (fields
        (field (name "BOM_Manufacturer Part") "MFR0W8F2200A50")
        (field (name "BOM_Supplier Part") "C63394")
      )
      (libsource (lib "") (part "MFR0W8F2200A50"))
    )
    (comp (ref "R27")
      (value "220")
      (fields
        (field (name "BOM_Manufacturer Part") "MFR0W8F2200A50")
        (field (name "BOM_Supplier Part") "C63394")
      )
      (libsource (lib "") (part "MFR0W8F2200A50"))
    )
    (comp (ref "R28")
      (value "220")
      (fields
        (field (name "BOM_Manufacturer Part") "MFR0W8F2200A50")
        (field (name "BOM_Supplier Part") "C63394")
      )
      (libsource (lib "") (part "MFR0W8F2200A50"))
    )
    (comp (ref "R29")
      (value "220")
      (fields
        (field (name "BOM_Manufacturer Part") "MFR0W8F2200A50")
        (field (name "BOM_Supplier Part") "C63394")
      )
      (libsource (lib "") (part "MFR0W8F2200A50"))
    )
    (comp (ref "U13")
      (value "SN74LS245N")
      (fields (field (name "BOM_Supplier Part") "C352966"))
      (libsource (lib "") (part "SN74LS245N"))
    )
    (comp (ref "U14")
      (value "XD74LS161")
      (fields (field (name "BOM_Supplier Part") "C609766"))
      (libsource (lib "") (part "XD74LS161"))
    )
    (comp (ref "U15")
      (value "XD74LS00")
      (fields (field (name "BOM_Supplier Part") "C556265"))
      (libsource (lib "") (part "XD74LS00"))
    )
    (comp (ref "LED4")
      (value "333-2SYGD/S530-E2-L")
      (fields (field (name "BOM_Supplier Part") "C99697"))
      (libsource (lib "") (part "333-2SYGD/S530-E2-L"))
    )
    (comp (ref "LED5")
      (value "333-2SYGD/S530-E2-L")
      (fields (field (name "BOM_Supplier Part") "C99697"))
      (libsource (lib "") (part "333-2SYGD/S530-E2-L"))
    )
    (comp (ref "LED6")
      (value "333-2SYGD/S530-E2-L")
      (fields (field (name "BOM_Supplier Part") "C99697"))
      (libsource (lib "") (part "333-2SYGD/S530-E2-L"))
    )
    (comp (ref "LED7")
      (value "333-2SYGD/S530-E2-L")
      (fields (field (name "BOM_Supplier Part") "C99697"))
      (libsource (lib "") (part "333-2SYGD/S530-E2-L"))
    )
    (comp (ref "LED8")
      (value "333-2SYGD/S530-E2-L")
      (fields (field (name "BOM_Supplier Part") "C99697"))
      (libsource (lib "") (part "333-2SYGD/S530-E2-L"))
    )
    (comp (ref "LED9")
      (value "333-2SYGD/S530-E2-L")
      (fields (field (name "BOM_Supplier Part") "C99697"))
      (libsource (lib "") (part "333-2SYGD/S530-E2-L"))
    )
    (comp (ref "LED10")
      (value "333-2SYGD/S530-E2-L")
      (fields (field (name "BOM_Supplier Part") "C99697"))
      (libsource (lib "") (part "333-2SYGD/S530-E2-L"))
    )
    (comp (ref "LED11")
      (value "333-2SYGD/S530-E2-L")
      (fields (field (name "BOM_Supplier Part") "C99697"))
      (libsource (lib "") (part "333-2SYGD/S530-E2-L"))
    )
    (comp (ref "R10")
      (value "220")
      (fields
        (field (name "BOM_Manufacturer Part") "MFR0W8F2200A50")
        (field (name "BOM_Supplier Part") "C63394")
      )
      (libsource (lib "") (part "MFR0W8F2200A50"))
    )
    (comp (ref "R11")
      (value "220")
      (fields
        (field (name "BOM_Manufacturer Part") "MFR0W8F2200A50")
        (field (name "BOM_Supplier Part") "C63394")
      )
      (libsource (lib "") (part "MFR0W8F2200A50"))
    )
    (comp (ref "R12")
      (value "220")
      (fields
        (field (name "BOM_Manufacturer Part") "MFR0W8F2200A50")
        (field (name "BOM_Supplier Part") "C63394")
      )
      (libsource (lib "") (part "MFR0W8F2200A50"))
    )
    (comp (ref "R13")
      (value "220")
      (fields
        (field (name "BOM_Manufacturer Part") "MFR0W8F2200A50")
        (field (name "BOM_Supplier Part") "C63394")
      )
      (libsource (lib "") (part "MFR0W8F2200A50"))
    )
    (comp (ref "R14")
      (value "220")
      (fields
        (field (name "BOM_Manufacturer Part") "MFR0W8F2200A50")
        (field (name "BOM_Supplier Part") "C63394")
      )
      (libsource (lib "") (part "MFR0W8F2200A50"))
    )
    (comp (ref "R15")
      (value "220")
      (fields
        (field (name "BOM_Manufacturer Part") "MFR0W8F2200A50")
        (field (name "BOM_Supplier Part") "C63394")
      )
      (libsource (lib "") (part "MFR0W8F2200A50"))
    )
    (comp (ref "R16")
      (value "220")
      (fields
        (field (name "BOM_Manufacturer Part") "MFR0W8F2200A50")
        (field (name "BOM_Supplier Part") "C63394")
      )
      (libsource (lib "") (part "MFR0W8F2200A50"))
    )
    (comp (ref "R17")
      (value "220")
      (fields
        (field (name "BOM_Manufacturer Part") "MFR0W8F2200A50")
        (field (name "BOM_Supplier Part") "C63394")
      )
      (libsource (lib "") (part "MFR0W8F2200A50"))
    )
    (comp (ref "U7")
      (value "SN74LS245N")
      (fields (field (name "BOM_Supplier Part") "C352966"))
      (libsource (lib "") (part "SN74LS245N"))
    )
    (comp (ref "U8")
      (value "74LS173 4 BIT D REGISTER")
      (libsource (lib "") (part "74LS173 4 BIT D REGISTER"))
    )
    (comp (ref "U9")
      (value "74LS173 4 BIT D REGISTER")
      (libsource (lib "") (part "74LS173 4 BIT D REGISTER"))
    )
    (comp (ref "LED12")
      (value "333-2SYGD/S530-E2-L")
      (fields (field (name "BOM_Supplier Part") "C99697"))
      (libsource (lib "") (part "333-2SYGD/S530-E2-L"))
    )
    (comp (ref "LED13")
      (value "333-2SYGD/S530-E2-L")
      (fields (field (name "BOM_Supplier Part") "C99697"))
      (libsource (lib "") (part "333-2SYGD/S530-E2-L"))
    )
    (comp (ref "LED14")
      (value "333-2SYGD/S530-E2-L")
      (fields (field (name "BOM_Supplier Part") "C99697"))
      (libsource (lib "") (part "333-2SYGD/S530-E2-L"))
    )
    (comp (ref "LED15")
      (value "333-2SYGD/S530-E2-L")
      (fields (field (name "BOM_Supplier Part") "C99697"))
      (libsource (lib "") (part "333-2SYGD/S530-E2-L"))
    )
    (comp (ref "LED16")
      (value "333-2SYGD/S530-E2-L")
      (fields (field (name "BOM_Supplier Part") "C99697"))
      (libsource (lib "") (part "333-2SYGD/S530-E2-L"))
    )
    (comp (ref "LED17")
      (value "333-2SYGD/S530-E2-L")
      (fields (field (name "BOM_Supplier Part") "C99697"))
      (libsource (lib "") (part "333-2SYGD/S530-E2-L"))
    )
    (comp (ref "LED18")
      (value "333-2SYGD/S530-E2-L")
      (fields (field (name "BOM_Supplier Part") "C99697"))
      (libsource (lib "") (part "333-2SYGD/S530-E2-L"))
    )
    (comp (ref "LED19")
      (value "333-2SYGD/S530-E2-L")
      (fields (field (name "BOM_Supplier Part") "C99697"))
      (libsource (lib "") (part "333-2SYGD/S530-E2-L"))
    )
    (comp (ref "R18")
      (value "220")
      (fields
        (field (name "BOM_Manufacturer Part") "MFR0W8F2200A50")
        (field (name "BOM_Supplier Part") "C63394")
      )
      (libsource (lib "") (part "MFR0W8F2200A50"))
    )
    (comp (ref "R19")
      (value "220")
      (fields
        (field (name "BOM_Manufacturer Part") "MFR0W8F2200A50")
        (field (name "BOM_Supplier Part") "C63394")
      )
      (libsource (lib "") (part "MFR0W8F2200A50"))
    )
    (comp (ref "R20")
      (value "220")
      (fields
        (field (name "BOM_Manufacturer Part") "MFR0W8F2200A50")
        (field (name "BOM_Supplier Part") "C63394")
      )
      (libsource (lib "") (part "MFR0W8F2200A50"))
    )
    (comp (ref "R21")
      (value "220")
      (fields
        (field (name "BOM_Manufacturer Part") "MFR0W8F2200A50")
        (field (name "BOM_Supplier Part") "C63394")
      )
      (libsource (lib "") (part "MFR0W8F2200A50"))
    )
    (comp (ref "R22")
      (value "220")
      (fields
        (field (name "BOM_Manufacturer Part") "MFR0W8F2200A50")
        (field (name "BOM_Supplier Part") "C63394")
      )
      (libsource (lib "") (part "MFR0W8F2200A50"))
    )
    (comp (ref "R23")
      (value "220")
      (fields
        (field (name "BOM_Manufacturer Part") "MFR0W8F2200A50")
        (field (name "BOM_Supplier Part") "C63394")
      )
      (libsource (lib "") (part "MFR0W8F2200A50"))
    )
    (comp (ref "R24")
      (value "220")
      (fields
        (field (name "BOM_Manufacturer Part") "MFR0W8F2200A50")
        (field (name "BOM_Supplier Part") "C63394")
      )
      (libsource (lib "") (part "MFR0W8F2200A50"))
    )
    (comp (ref "R25")
      (value "220")
      (fields
        (field (name "BOM_Manufacturer Part") "MFR0W8F2200A50")
        (field (name "BOM_Supplier Part") "C63394")
      )
      (libsource (lib "") (part "MFR0W8F2200A50"))
    )
    (comp (ref "U10")
      (value "SN74LS245N")
      (fields (field (name "BOM_Supplier Part") "C352966"))
      (libsource (lib "") (part "SN74LS245N"))
    )
    (comp (ref "U11")
      (value "74LS173 4 BIT D REGISTER")
      (libsource (lib "") (part "74LS173 4 BIT D REGISTER"))
    )
    (comp (ref "U12")
      (value "74LS173 4 BIT D REGISTER")
      (libsource (lib "") (part "74LS173 4 BIT D REGISTER"))
    )
    (comp (ref "LED24")
      (value "333-2SYGD/S530-E2-L")
      (fields (field (name "BOM_Supplier Part") "C99697"))
      (libsource (lib "") (part "333-2SYGD/S530-E2-L"))
    )
    (comp (ref "LED25")
      (value "333-2SYGD/S530-E2-L")
      (fields (field (name "BOM_Supplier Part") "C99697"))
      (libsource (lib "") (part "333-2SYGD/S530-E2-L"))
    )
    (comp (ref "LED26")
      (value "333-2SYGD/S530-E2-L")
      (fields (field (name "BOM_Supplier Part") "C99697"))
      (libsource (lib "") (part "333-2SYGD/S530-E2-L"))
    )
    (comp (ref "LED27")
      (value "333-2SYGD/S530-E2-L")
      (fields (field (name "BOM_Supplier Part") "C99697"))
      (libsource (lib "") (part "333-2SYGD/S530-E2-L"))
    )
    (comp (ref "LED28")
      (value "333-2SYGD/S530-E2-L")
      (fields (field (name "BOM_Supplier Part") "C99697"))
      (libsource (lib "") (part "333-2SYGD/S530-E2-L"))
    )
    (comp (ref "LED29")
      (value "333-2SYGD/S530-E2-L")
      (fields (field (name "BOM_Supplier Part") "C99697"))
      (libsource (lib "") (part "333-2SYGD/S530-E2-L"))
    )
    (comp (ref "LED30")
      (value "333-2SYGD/S530-E2-L")
      (fields (field (name "BOM_Supplier Part") "C99697"))
      (libsource (lib "") (part "333-2SYGD/S530-E2-L"))
    )
    (comp (ref "LED31")
      (value "333-2SYGD/S530-E2-L")
      (fields (field (name "BOM_Supplier Part") "C99697"))
      (libsource (lib "") (part "333-2SYGD/S530-E2-L"))
    )
    (comp (ref "R30")
      (value "220")
      (fields
        (field (name "BOM_Manufacturer Part") "MFR0W8F2200A50")
        (field (name "BOM_Supplier Part") "C63394")
      )
      (libsource (lib "") (part "MFR0W8F2200A50"))
    )
    (comp (ref "R31")
      (value "220")
      (fields
        (field (name "BOM_Manufacturer Part") "MFR0W8F2200A50")
        (field (name "BOM_Supplier Part") "C63394")
      )
      (libsource (lib "") (part "MFR0W8F2200A50"))
    )
    (comp (ref "R32")
      (value "220")
      (fields
        (field (name "BOM_Manufacturer Part") "MFR0W8F2200A50")
        (field (name "BOM_Supplier Part") "C63394")
      )
      (libsource (lib "") (part "MFR0W8F2200A50"))
    )
    (comp (ref "R33")
      (value "220")
      (fields
        (field (name "BOM_Manufacturer Part") "MFR0W8F2200A50")
        (field (name "BOM_Supplier Part") "C63394")
      )
      (libsource (lib "") (part "MFR0W8F2200A50"))
    )
    (comp (ref "R34")
      (value "220")
      (fields
        (field (name "BOM_Manufacturer Part") "MFR0W8F2200A50")
        (field (name "BOM_Supplier Part") "C63394")
      )
      (libsource (lib "") (part "MFR0W8F2200A50"))
    )
    (comp (ref "R35")
      (value "220")
      (fields
        (field (name "BOM_Manufacturer Part") "MFR0W8F2200A50")
        (field (name "BOM_Supplier Part") "C63394")
      )
      (libsource (lib "") (part "MFR0W8F2200A50"))
    )
    (comp (ref "R36")
      (value "220")
      (fields
        (field (name "BOM_Manufacturer Part") "MFR0W8F2200A50")
        (field (name "BOM_Supplier Part") "C63394")
      )
      (libsource (lib "") (part "MFR0W8F2200A50"))
    )
    (comp (ref "R37")
      (value "220")
      (fields
        (field (name "BOM_Manufacturer Part") "MFR0W8F2200A50")
        (field (name "BOM_Supplier Part") "C63394")
      )
      (libsource (lib "") (part "MFR0W8F2200A50"))
    )
    (comp (ref "U16")
      (value "74LS173 4 BIT D REGISTER")
      (libsource (lib "") (part "74LS173 4 BIT D REGISTER"))
    )
    (comp (ref "U17")
      (value "74LS173 4 BIT D REGISTER")
      (libsource (lib "") (part "74LS173 4 BIT D REGISTER"))
    )
    (comp (ref "U18")
      (value "SN74LS245N")
      (fields (field (name "BOM_Supplier Part") "C352966"))
      (libsource (lib "") (part "SN74LS245N"))
    )
    (comp (ref "LED32")
      (value "333-2SYGD/S530-E2-L")
      (fields (field (name "BOM_Supplier Part") "C99697"))
      (libsource (lib "") (part "333-2SYGD/S530-E2-L"))
    )
    (comp (ref "LED33")
      (value "333-2SYGD/S530-E2-L")
      (fields (field (name "BOM_Supplier Part") "C99697"))
      (libsource (lib "") (part "333-2SYGD/S530-E2-L"))
    )
    (comp (ref "LED34")
      (value "333-2SYGD/S530-E2-L")
      (fields (field (name "BOM_Supplier Part") "C99697"))
      (libsource (lib "") (part "333-2SYGD/S530-E2-L"))
    )
    (comp (ref "LED35")
      (value "333-2SYGD/S530-E2-L")
      (fields (field (name "BOM_Supplier Part") "C99697"))
      (libsource (lib "") (part "333-2SYGD/S530-E2-L"))
    )
    (comp (ref "LED36")
      (value "333-2SYGD/S530-E2-L")
      (fields (field (name "BOM_Supplier Part") "C99697"))
      (libsource (lib "") (part "333-2SYGD/S530-E2-L"))
    )
    (comp (ref "LED37")
      (value "333-2SYGD/S530-E2-L")
      (fields (field (name "BOM_Supplier Part") "C99697"))
      (libsource (lib "") (part "333-2SYGD/S530-E2-L"))
    )
    (comp (ref "LED38")
      (value "333-2SYGD/S530-E2-L")
      (fields (field (name "BOM_Supplier Part") "C99697"))
      (libsource (lib "") (part "333-2SYGD/S530-E2-L"))
    )
    (comp (ref "LED39")
      (value "333-2SYGD/S530-E2-L")
      (fields (field (name "BOM_Supplier Part") "C99697"))
      (libsource (lib "") (part "333-2SYGD/S530-E2-L"))
    )
    (comp (ref "R38")
      (value "220")
      (fields
        (field (name "BOM_Manufacturer Part") "MFR0W8F2200A50")
        (field (name "BOM_Supplier Part") "C63394")
      )
      (libsource (lib "") (part "MFR0W8F2200A50"))
    )
    (comp (ref "R39")
      (value "220")
      (fields
        (field (name "BOM_Manufacturer Part") "MFR0W8F2200A50")
        (field (name "BOM_Supplier Part") "C63394")
      )
      (libsource (lib "") (part "MFR0W8F2200A50"))
    )
    (comp (ref "R40")
      (value "220")
      (fields
        (field (name "BOM_Manufacturer Part") "MFR0W8F2200A50")
        (field (name "BOM_Supplier Part") "C63394")
      )
      (libsource (lib "") (part "MFR0W8F2200A50"))
    )
    (comp (ref "R41")
      (value "220")
      (fields
        (field (name "BOM_Manufacturer Part") "MFR0W8F2200A50")
        (field (name "BOM_Supplier Part") "C63394")
      )
      (libsource (lib "") (part "MFR0W8F2200A50"))
    )
    (comp (ref "R42")
      (value "220")
      (fields
        (field (name "BOM_Manufacturer Part") "MFR0W8F2200A50")
        (field (name "BOM_Supplier Part") "C63394")
      )
      (libsource (lib "") (part "MFR0W8F2200A50"))
    )
    (comp (ref "R43")
      (value "220")
      (fields
        (field (name "BOM_Manufacturer Part") "MFR0W8F2200A50")
        (field (name "BOM_Supplier Part") "C63394")
      )
      (libsource (lib "") (part "MFR0W8F2200A50"))
    )
    (comp (ref "R44")
      (value "220")
      (fields
        (field (name "BOM_Manufacturer Part") "MFR0W8F2200A50")
        (field (name "BOM_Supplier Part") "C63394")
      )
      (libsource (lib "") (part "MFR0W8F2200A50"))
    )
    (comp (ref "R45")
      (value "220")
      (fields
        (field (name "BOM_Manufacturer Part") "MFR0W8F2200A50")
        (field (name "BOM_Supplier Part") "C63394")
      )
      (libsource (lib "") (part "MFR0W8F2200A50"))
    )
    (comp (ref "U19")
      (value "SN74LS245N")
      (fields (field (name "BOM_Supplier Part") "C352966"))
      (libsource (lib "") (part "SN74LS245N"))
    )
    (comp (ref "U20") (value "74LS283") (libsource (lib "") (part "74LS283")))
    (comp (ref "U21") (value "74LS283") (libsource (lib "") (part "74LS283")))
    (comp (ref "U22")
      (value "74LS86")
      (fields (field (name "BOM_Supplier Part") "C21802"))
      (libsource (lib "") (part "74LS86"))
    )
    (comp (ref "U23")
      (value "74LS86")
      (fields (field (name "BOM_Supplier Part") "C21802"))
      (libsource (lib "") (part "74LS86"))
    )
    (comp (ref "LED40")
      (value "333-2SYGD/S530-E2-L")
      (fields (field (name "BOM_Supplier Part") "C99697"))
      (libsource (lib "") (part "333-2SYGD/S530-E2-L"))
    )
    (comp (ref "LED41")
      (value "333-2SYGD/S530-E2-L")
      (fields (field (name "BOM_Supplier Part") "C99697"))
      (libsource (lib "") (part "333-2SYGD/S530-E2-L"))
    )
    (comp (ref "LED42")
      (value "333-2SYGD/S530-E2-L")
      (fields (field (name "BOM_Supplier Part") "C99697"))
      (libsource (lib "") (part "333-2SYGD/S530-E2-L"))
    )
    (comp (ref "LED43")
      (value "333-2SYGD/S530-E2-L")
      (fields (field (name "BOM_Supplier Part") "C99697"))
      (libsource (lib "") (part "333-2SYGD/S530-E2-L"))
    )
    (comp (ref "LED44")
      (value "333-2SYGD/S530-E2-L")
      (fields (field (name "BOM_Supplier Part") "C99697"))
      (libsource (lib "") (part "333-2SYGD/S530-E2-L"))
    )
    (comp (ref "LED45")
      (value "333-2SYGD/S530-E2-L")
      (fields (field (name "BOM_Supplier Part") "C99697"))
      (libsource (lib "") (part "333-2SYGD/S530-E2-L"))
    )
    (comp (ref "LED46")
      (value "333-2SYGD/S530-E2-L")
      (fields (field (name "BOM_Supplier Part") "C99697"))
      (libsource (lib "") (part "333-2SYGD/S530-E2-L"))
    )
    (comp (ref "LED47")
      (value "333-2SYGD/S530-E2-L")
      (fields (field (name "BOM_Supplier Part") "C99697"))
      (libsource (lib "") (part "333-2SYGD/S530-E2-L"))
    )
    (comp (ref "R46")
      (value "220")
      (fields
        (field (name "BOM_Manufacturer Part") "MFR0W8F2200A50")
        (field (name "BOM_Supplier Part") "C63394")
      )
      (libsource (lib "") (part "MFR0W8F2200A50_1"))
    )
    (comp (ref "R47")
      (value "220")
      (fields
        (field (name "BOM_Manufacturer Part") "MFR0W8F2200A50")
        (field (name "BOM_Supplier Part") "C63394")
      )
      (libsource (lib "") (part "MFR0W8F2200A50_1"))
    )
    (comp (ref "R48")
      (value "220")
      (fields
        (field (name "BOM_Manufacturer Part") "MFR0W8F2200A50")
        (field (name "BOM_Supplier Part") "C63394")
      )
      (libsource (lib "") (part "MFR0W8F2200A50_1"))
    )
    (comp (ref "R49")
      (value "220")
      (fields
        (field (name "BOM_Manufacturer Part") "MFR0W8F2200A50")
        (field (name "BOM_Supplier Part") "C63394")
      )
      (libsource (lib "") (part "MFR0W8F2200A50_1"))
    )
    (comp (ref "R50")
      (value "220")
      (fields
        (field (name "BOM_Manufacturer Part") "MFR0W8F2200A50")
        (field (name "BOM_Supplier Part") "C63394")
      )
      (libsource (lib "") (part "MFR0W8F2200A50_1"))
    )
    (comp (ref "R51")
      (value "220")
      (fields
        (field (name "BOM_Manufacturer Part") "MFR0W8F2200A50")
        (field (name "BOM_Supplier Part") "C63394")
      )
      (libsource (lib "") (part "MFR0W8F2200A50_1"))
    )
    (comp (ref "R52")
      (value "220")
      (fields
        (field (name "BOM_Manufacturer Part") "MFR0W8F2200A50")
        (field (name "BOM_Supplier Part") "C63394")
      )
      (libsource (lib "") (part "MFR0W8F2200A50_1"))
    )
    (comp (ref "R53")
      (value "220")
      (fields
        (field (name "BOM_Manufacturer Part") "MFR0W8F2200A50")
        (field (name "BOM_Supplier Part") "C63394")
      )
      (libsource (lib "") (part "MFR0W8F2200A50_1"))
    )
    (comp (ref "R54")
      (value "220")
      (fields
        (field (name "BOM_Manufacturer Part") "MFR0W8F2200A50")
        (field (name "BOM_Supplier Part") "C63394")
      )
      (libsource (lib "") (part "MFR0W8F2200A50"))
    )
    (comp (ref "R55")
      (value "220")
      (fields
        (field (name "BOM_Manufacturer Part") "MFR0W8F2200A50")
        (field (name "BOM_Supplier Part") "C63394")
      )
      (libsource (lib "") (part "MFR0W8F2200A50"))
    )
    (comp (ref "R56")
      (value "220")
      (fields
        (field (name "BOM_Manufacturer Part") "MFR0W8F2200A50")
        (field (name "BOM_Supplier Part") "C63394")
      )
      (libsource (lib "") (part "MFR0W8F2200A50"))
    )
    (comp (ref "R57")
      (value "220")
      (fields
        (field (name "BOM_Manufacturer Part") "MFR0W8F2200A50")
        (field (name "BOM_Supplier Part") "C63394")
      )
      (libsource (lib "") (part "MFR0W8F2200A50"))
    )
    (comp (ref "R58")
      (value "220")
      (fields
        (field (name "BOM_Manufacturer Part") "MFR0W8F2200A50")
        (field (name "BOM_Supplier Part") "C63394")
      )
      (libsource (lib "") (part "MFR0W8F2200A50"))
    )
    (comp (ref "R59")
      (value "220")
      (fields
        (field (name "BOM_Manufacturer Part") "MFR0W8F2200A50")
        (field (name "BOM_Supplier Part") "C63394")
      )
      (libsource (lib "") (part "MFR0W8F2200A50"))
    )
    (comp (ref "R60")
      (value "220")
      (fields
        (field (name "BOM_Manufacturer Part") "MFR0W8F2200A50")
        (field (name "BOM_Supplier Part") "C63394")
      )
      (libsource (lib "") (part "MFR0W8F2200A50"))
    )
    (comp (ref "R61")
      (value "220")
      (fields
        (field (name "BOM_Manufacturer Part") "MFR0W8F2200A50")
        (field (name "BOM_Supplier Part") "C63394")
      )
      (libsource (lib "") (part "MFR0W8F2200A50"))
    )
  )
  (nets
    (net (code "1") (name "A0") (class "Default")
      (node (ref "U10") (pin "19") (pinfunction "#OE_19") (pintype "unspecified"))
      (node (ref "U7") (pin "19") (pinfunction "#OE_19") (pintype "unspecified"))
    )
    (net (code "2") (name "A1") (class "Default")
      (node (ref "U11") (pin "10") (pinfunction "G2i_10") (pintype "unspecified"))
      (node (ref "U11") (pin "9") (pinfunction "G1i_9") (pintype "unspecified"))
      (node (ref "U12") (pin "10") (pinfunction "G2i_10") (pintype "unspecified"))
      (node (ref "U12") (pin "9") (pinfunction "G1i_9") (pintype "unspecified"))
      (node (ref "U8") (pin "10") (pinfunction "G2i_10") (pintype "unspecified"))
      (node (ref "U8") (pin "9") (pinfunction "G1i_9") (pintype "unspecified"))
      (node (ref "U9") (pin "10") (pinfunction "G2i_10") (pintype "unspecified"))
      (node (ref "U9") (pin "9") (pinfunction "G1i_9") (pintype "unspecified"))
    )
    (net (code "3") (name "ALU_Carry_Out") (class "Default")
      (node (ref "U15") (pin "1") (pinfunction "1A_1") (pintype "unspecified"))
      (node (ref "U21") (pin "9") (pinfunction "C4_9") (pintype "unspecified"))
    )
    (net (code "4") (name "Bus1") (class "Default")
      (node (ref "LED47") (pin "1") (pinfunction "A_1") (pintype "input"))
      (node (ref "R58") (pin "2") (pinfunction "2_2") (pintype "unspecified"))
      (node (ref "U10") (pin "11") (pinfunction "B8_11") (pintype "unspecified"))
      (node (ref "U12") (pin "11") (pinfunction "4D_11") (pintype "unspecified"))
      (node (ref "U13") (pin "9") (pinfunction "A8_9") (pintype "unspecified"))
      (node (ref "U14") (pin "3") (pinfunction "A_3") (pintype "unspecified"))
      (node (ref "U16") (pin "14") (pinfunction "1D_14") (pintype "unspecified"))
      (node (ref "U18") (pin "18") (pinfunction "B1_18") (pintype "unspecified"))
      (node (ref "U19") (pin "11") (pinfunction "B8_11") (pintype "unspecified"))
      (node (ref "U7") (pin "11") (pinfunction "B8_11") (pintype "unspecified"))
      (node (ref "U9") (pin "11") (pinfunction "4D_11") (pintype "unspecified"))
    )
    (net (code "5") (name "Bus2") (class "Default")
      (node (ref "LED46") (pin "1") (pinfunction "A_1") (pintype "input"))
      (node (ref "R59") (pin "2") (pinfunction "2_2") (pintype "unspecified"))
      (node (ref "U10") (pin "12") (pinfunction "B7_12") (pintype "unspecified"))
      (node (ref "U12") (pin "12") (pinfunction "3D_12") (pintype "unspecified"))
      (node (ref "U13") (pin "8") (pinfunction "A7_8") (pintype "unspecified"))
      (node (ref "U14") (pin "4") (pinfunction "B_4") (pintype "unspecified"))
      (node (ref "U16") (pin "13") (pinfunction "2D_13") (pintype "unspecified"))
      (node (ref "U18") (pin "17") (pinfunction "B2_17") (pintype "unspecified"))
      (node (ref "U19") (pin "12") (pinfunction "B7_12") (pintype "unspecified"))
      (node (ref "U7") (pin "12") (pinfunction "B7_12") (pintype "unspecified"))
      (node (ref "U9") (pin "12") (pinfunction "3D_12") (pintype "unspecified"))
    )
    (net (code "6") (name "Bus3") (class "Default")
      (node (ref "LED45") (pin "1") (pinfunction "A_1") (pintype "input"))
      (node (ref "R60") (pin "2") (pinfunction "2_2") (pintype "unspecified"))
      (node (ref "U10") (pin "13") (pinfunction "B6_13") (pintype "unspecified"))
      (node (ref "U12") (pin "13") (pinfunction "2D_13") (pintype "unspecified"))
      (node (ref "U13") (pin "7") (pinfunction "A6_7") (pintype "unspecified"))
      (node (ref "U14") (pin "5") (pinfunction "C_5") (pintype "unspecified"))
      (node (ref "U16") (pin "12") (pinfunction "3D_12") (pintype "unspecified"))
      (node (ref "U18") (pin "16") (pinfunction "B3_16") (pintype "unspecified"))
      (node (ref "U19") (pin "13") (pinfunction "B6_13") (pintype "unspecified"))
      (node (ref "U7") (pin "13") (pinfunction "B6_13") (pintype "unspecified"))
      (node (ref "U9") (pin "13") (pinfunction "2D_13") (pintype "unspecified"))
    )
    (net (code "7") (name "Bus4") (class "Default")
      (node (ref "LED44") (pin "1") (pinfunction "A_1") (pintype "input"))
      (node (ref "R61") (pin "2") (pinfunction "2_2") (pintype "unspecified"))
      (node (ref "U10") (pin "14") (pinfunction "B5_14") (pintype "unspecified"))
      (node (ref "U12") (pin "14") (pinfunction "1D_14") (pintype "unspecified"))
      (node (ref "U13") (pin "6") (pinfunction "A5_6") (pintype "unspecified"))
      (node (ref "U14") (pin "6") (pinfunction "D_6") (pintype "unspecified"))
      (node (ref "U16") (pin "11") (pinfunction "4D_11") (pintype "unspecified"))
      (node (ref "U18") (pin "15") (pinfunction "B4_15") (pintype "unspecified"))
      (node (ref "U19") (pin "14") (pinfunction "B5_14") (pintype "unspecified"))
      (node (ref "U7") (pin "14") (pinfunction "B5_14") (pintype "unspecified"))
      (node (ref "U9") (pin "14") (pinfunction "1D_14") (pintype "unspecified"))
    )
    (net (code "8") (name "Bus5") (class "Default")
      (node (ref "LED43") (pin "1") (pinfunction "A_1") (pintype "input"))
      (node (ref "R57") (pin "1") (pinfunction "1_1") (pintype "unspecified"))
      (node (ref "U10") (pin "15") (pinfunction "B4_15") (pintype "unspecified"))
      (node (ref "U11") (pin "11") (pinfunction "4D_11") (pintype "unspecified"))
      (node (ref "U17") (pin "14") (pinfunction "1D_14") (pintype "unspecified"))
      (node (ref "U18") (pin "14") (pinfunction "B5_14") (pintype "unspecified"))
      (node (ref "U19") (pin "15") (pinfunction "B4_15") (pintype "unspecified"))
      (node (ref "U7") (pin "15") (pinfunction "B4_15") (pintype "unspecified"))
      (node (ref "U8") (pin "11") (pinfunction "4D_11") (pintype "unspecified"))
    )
    (net (code "9") (name "Bus6") (class "Default")
      (node (ref "LED42") (pin "1") (pinfunction "A_1") (pintype "input"))
      (node (ref "R56") (pin "1") (pinfunction "1_1") (pintype "unspecified"))
      (node (ref "U10") (pin "16") (pinfunction "B3_16") (pintype "unspecified"))
      (node (ref "U11") (pin "12") (pinfunction "3D_12") (pintype "unspecified"))
      (node (ref "U17") (pin "13") (pinfunction "2D_13") (pintype "unspecified"))
      (node (ref "U18") (pin "13") (pinfunction "B6_13") (pintype "unspecified"))
      (node (ref "U19") (pin "16") (pinfunction "B3_16") (pintype "unspecified"))
      (node (ref "U7") (pin "16") (pinfunction "B3_16") (pintype "unspecified"))
      (node (ref "U8") (pin "12") (pinfunction "3D_12") (pintype "unspecified"))
    )
    (net (code "10") (name "Bus7") (class "Default")
      (node (ref "LED41") (pin "1") (pinfunction "A_1") (pintype "input"))
      (node (ref "R55") (pin "1") (pinfunction "1_1") (pintype "unspecified"))
      (node (ref "U10") (pin "17") (pinfunction "B2_17") (pintype "unspecified"))
      (node (ref "U11") (pin "13") (pinfunction "2D_13") (pintype "unspecified"))
      (node (ref "U17") (pin "12") (pinfunction "3D_12") (pintype "unspecified"))
      (node (ref "U18") (pin "12") (pinfunction "B7_12") (pintype "unspecified"))
      (node (ref "U19") (pin "17") (pinfunction "B2_17") (pintype "unspecified"))
      (node (ref "U7") (pin "17") (pinfunction "B2_17") (pintype "unspecified"))
      (node (ref "U8") (pin "13") (pinfunction "2D_13") (pintype "unspecified"))
    )
    (net (code "11") (name "Bus8") (class "Default")
      (node (ref "LED40") (pin "1") (pinfunction "A_1") (pintype "input"))
      (node (ref "R54") (pin "1") (pinfunction "1_1") (pintype "unspecified"))
      (node (ref "U10") (pin "18") (pinfunction "B1_18") (pintype "unspecified"))
      (node (ref "U11") (pin "14") (pinfunction "1D_14") (pintype "unspecified"))
      (node (ref "U17") (pin "11") (pinfunction "4D_11") (pintype "unspecified"))
      (node (ref "U18") (pin "11") (pinfunction "B8_11") (pintype "unspecified"))
      (node (ref "U19") (pin "18") (pinfunction "B1_18") (pintype "unspecified"))
      (node (ref "U7") (pin "18") (pinfunction "B1_18") (pintype "unspecified"))
      (node (ref "U8") (pin "14") (pinfunction "1D_14") (pintype "unspecified"))
    )
    (net (code "12") (name "CE_Counter_Enable") (class "Default")
      (node (ref "U14") (pin "10") (pinfunction "Enable_T_10") (pintype "unspecified"))
      (node (ref "U14") (pin "7") (pinfunction "Enable_P_7") (pintype "unspecified"))
    )
    (net (code "13") (name "CLK") (class "Default")
      (node (ref "LED3") (pin "1") (pinfunction "A_1") (pintype "input"))
      (node (ref "U11") (pin "7") (pinfunction "CLK_7") (pintype "unspecified"))
      (node (ref "U12") (pin "7") (pinfunction "CLK_7") (pintype "unspecified"))
      (node (ref "U14") (pin "2") (pinfunction "Clock_2") (pintype "unspecified"))
      (node (ref "U16") (pin "7") (pinfunction "CLK_7") (pintype "unspecified"))
      (node (ref "U17") (pin "7") (pinfunction "CLK_7") (pintype "unspecified"))
      (node (ref "U3") (pin "13") (pinfunction "6A_13") (pintype "unspecified"))
      (node (ref "U4") (pin "8") (pinfunction "4Y_8") (pintype "unspecified"))
      (node (ref "U8") (pin "7") (pinfunction "CLK_7") (pintype "unspecified"))
      (node (ref "U9") (pin "7") (pinfunction "CLK_7") (pintype "unspecified"))
    )
    (net (code "14") (name "CLR") (class "Default")
      (node (ref "U14") (pin "1") (pinfunction "Clear_1") (pintype "unspecified"))
      (node (ref "U16") (pin "15") (pinfunction "CLR_15") (pintype "unspecified"))
      (node (ref "U17") (pin "15") (pinfunction "CLR_15") (pintype "unspecified"))
    )
    (net (code "15") (name "Clear") (class "Default")
      (node (ref "U11") (pin "15") (pinfunction "CLR_15") (pintype "unspecified"))
      (node (ref "U12") (pin "15") (pinfunction "CLR_15") (pintype "unspecified"))
      (node (ref "U8") (pin "15") (pinfunction "CLR_15") (pintype "unspecified"))
      (node (ref "U9") (pin "15") (pinfunction "CLR_15") (pintype "unspecified"))
    )
    (net (code "16") (name "CounterOut") (class "Default")
      (node (ref "U13") (pin "19") (pinfunction "#OE_19") (pintype "unspecified"))
    )
    (net (code "17") (name "EO") (class "Default")
      (node (ref "U19") (pin "19") (pinfunction "#OE_19") (pintype "unspecified"))
    )
    (net (code "18") (name "GND") (class "Default")
      (node (ref "C1") (pin "1") (pinfunction "1_1") (pintype "unspecified"))
      (node (ref "C3") (pin "1") (pinfunction "1_1") (pintype "unspecified"))
      (node (ref "C4") (pin "1") (pinfunction "1_1") (pintype "unspecified"))
      (node (ref "C5") (pin "1") (pinfunction "1_1") (pintype "unspecified"))
      (node (ref "C6") (pin "2") (pinfunction "2_2") (pintype "unspecified"))
      (node (ref "C7") (pin "2") (pinfunction "2_2") (pintype "unspecified"))
      (node (ref "R10") (pin "1") (pinfunction "1_1") (pintype "unspecified"))
      (node (ref "R11") (pin "1") (pinfunction "1_1") (pintype "unspecified"))
      (node (ref "R12") (pin "1") (pinfunction "1_1") (pintype "unspecified"))
      (node (ref "R13") (pin "1") (pinfunction "1_1") (pintype "unspecified"))
      (node (ref "R14") (pin "1") (pinfunction "1_1") (pintype "unspecified"))
      (node (ref "R15") (pin "1") (pinfunction "1_1") (pintype "unspecified"))
      (node (ref "R16") (pin "1") (pinfunction "1_1") (pintype "unspecified"))
      (node (ref "R17") (pin "1") (pinfunction "1_1") (pintype "unspecified"))
      (node (ref "R18") (pin "1") (pinfunction "1_1") (pintype "unspecified"))
      (node (ref "R19") (pin "1") (pinfunction "1_1") (pintype "unspecified"))
      (node (ref "R20") (pin "1") (pinfunction "1_1") (pintype "unspecified"))
      (node (ref "R21") (pin "1") (pinfunction "1_1") (pintype "unspecified"))
      (node (ref "R22") (pin "1") (pinfunction "1_1") (pintype "unspecified"))
      (node (ref "R23") (pin "1") (pinfunction "1_1") (pintype "unspecified"))
      (node (ref "R24") (pin "1") (pinfunction "1_1") (pintype "unspecified"))
      (node (ref "R25") (pin "1") (pinfunction "1_1") (pintype "unspecified"))
      (node (ref "R26") (pin "2") (pinfunction "2_2") (pintype "unspecified"))
      (node (ref "R27") (pin "2") (pinfunction "2_2") (pintype "unspecified"))
      (node (ref "R28") (pin "2") (pinfunction "2_2") (pintype "unspecified"))
      (node (ref "R29") (pin "2") (pinfunction "2_2") (pintype "unspecified"))
      (node (ref "R30") (pin "1") (pinfunction "1_1") (pintype "unspecified"))
      (node (ref "R31") (pin "1") (pinfunction "1_1") (pintype "unspecified"))
      (node (ref "R32") (pin "1") (pinfunction "1_1") (pintype "unspecified"))
      (node (ref "R33") (pin "1") (pinfunction "1_1") (pintype "unspecified"))
      (node (ref "R34") (pin "1") (pinfunction "1_1") (pintype "unspecified"))
      (node (ref "R35") (pin "1") (pinfunction "1_1") (pintype "unspecified"))
      (node (ref "R36") (pin "1") (pinfunction "1_1") (pintype "unspecified"))
      (node (ref "R37") (pin "1") (pinfunction "1_1") (pintype "unspecified"))
      (node (ref "R38") (pin "1") (pinfunction "1_1") (pintype "unspecified"))
      (node (ref "R39") (pin "1") (pinfunction "1_1") (pintype "unspecified"))
      (node (ref "R4") (pin "2") (pinfunction "2_2") (pintype "input"))
      (node (ref "R40") (pin "1") (pinfunction "1_1") (pintype "unspecified"))
      (node (ref "R41") (pin "1") (pinfunction "1_1") (pintype "unspecified"))
      (node (ref "R42") (pin "1") (pinfunction "1_1") (pintype "unspecified"))
      (node (ref "R43") (pin "1") (pinfunction "1_1") (pintype "unspecified"))
      (node (ref "R44") (pin "1") (pinfunction "1_1") (pintype "unspecified"))
      (node (ref "R45") (pin "1") (pinfunction "1_1") (pintype "unspecified"))
      (node (ref "R46") (pin "2") (pinfunction "2_2") (pintype "unspecified"))
      (node (ref "R47") (pin "2") (pinfunction "2_2") (pintype "unspecified"))
      (node (ref "R48") (pin "2") (pinfunction "2_2") (pintype "unspecified"))
      (node (ref "R49") (pin "2") (pinfunction "2_2") (pintype "unspecified"))
      (node (ref "R50") (pin "2") (pinfunction "2_2") (pintype "unspecified"))
      (node (ref "R51") (pin "2") (pinfunction "2_2") (pintype "unspecified"))
      (node (ref "R52") (pin "2") (pinfunction "2_2") (pintype "unspecified"))
      (node (ref "R53") (pin "2") (pinfunction "2_2") (pintype "unspecified"))
      (node (ref "R54") (pin "2") (pinfunction "2_2") (pintype "unspecified"))
      (node (ref "R55") (pin "2") (pinfunction "2_2") (pintype "unspecified"))
      (node (ref "R56") (pin "2") (pinfunction "2_2") (pintype "unspecified"))
      (node (ref "R57") (pin "2") (pinfunction "2_2") (pintype "unspecified"))
      (node (ref "R58") (pin "1") (pinfunction "1_1") (pintype "unspecified"))
      (node (ref "R59") (pin "1") (pinfunction "1_1") (pintype "unspecified"))
      (node (ref "R60") (pin "1") (pinfunction "1_1") (pintype "unspecified"))
      (node (ref "R61") (pin "1") (pinfunction "1_1") (pintype "unspecified"))
      (node (ref "R7") (pin "1") (pinfunction "1_1") (pintype "input"))
      (node (ref "R8") (pin "2") (pinfunction "2_2") (pintype "input"))
      (node (ref "SW1") (pin "2") (pinfunction "2_2") (pintype "unspecified"))
      (node (ref "SW3") (pin "1") (pinfunction "1_1") (pintype "unspecified"))
      (node (ref "U1") (pin "1") (pinfunction "GND_1") (pintype "unspecified"))
      (node (ref "U10") (pin "10") (pinfunction "GND_10") (pintype "unspecified"))
      (node (ref "U11") (pin "1") (pinfunction "M_1") (pintype "unspecified"))
      (node (ref "U11") (pin "2") (pinfunction "N_2") (pintype "unspecified"))
      (node (ref "U11") (pin "8") (pinfunction "GND_8") (pintype "unspecified"))
      (node (ref "U12") (pin "1") (pinfunction "M_1") (pintype "unspecified"))
      (node (ref "U12") (pin "2") (pinfunction "N_2") (pintype "unspecified"))
      (node (ref "U12") (pin "8") (pinfunction "GND_8") (pintype "unspecified"))
      (node (ref "U13") (pin "1") (pinfunction "DIR_1") (pintype "unspecified"))
      (node (ref "U13") (pin "10") (pinfunction "GND_10") (pintype "unspecified"))
      (node (ref "U13") (pin "15") (pinfunction "B4_15") (pintype "unspecified"))
      (node (ref "U13") (pin "16") (pinfunction "B3_16") (pintype "unspecified"))
      (node (ref "U13") (pin "17") (pinfunction "B2_17") (pintype "unspecified"))
      (node (ref "U13") (pin "18") (pinfunction "B1_18") (pintype "unspecified"))
      (node (ref "U13") (pin "2") (pinfunction "A1_2") (pintype "unspecified"))
      (node (ref "U13") (pin "3") (pinfunction "A2_3") (pintype "unspecified"))
      (node (ref "U13") (pin "4") (pinfunction "A3_4") (pintype "unspecified"))
      (node (ref "U13") (pin "5") (pinfunction "A4_5") (pintype "unspecified"))
      (node (ref "U14") (pin "8") (pinfunction "GND_8") (pintype "unspecified"))
      (node (ref "U15") (pin "7") (pinfunction "GND_7") (pintype "unspecified"))
      (node (ref "U16") (pin "1") (pinfunction "M_1") (pintype "unspecified"))
      (node (ref "U16") (pin "2") (pinfunction "N_2") (pintype "unspecified"))
      (node (ref "U16") (pin "8") (pinfunction "GND_8") (pintype "unspecified"))
      (node (ref "U17") (pin "1") (pinfunction "M_1") (pintype "unspecified"))
      (node (ref "U17") (pin "2") (pinfunction "N_2") (pintype "unspecified"))
      (node (ref "U17") (pin "8") (pinfunction "GND_8") (pintype "unspecified"))
      (node (ref "U18") (pin "10") (pinfunction "GND_10") (pintype "unspecified"))
      (node (ref "U18") (pin "2") (pinfunction "A1_2") (pintype "unspecified"))
      (node (ref "U18") (pin "3") (pinfunction "A2_3") (pintype "unspecified"))
      (node (ref "U18") (pin "4") (pinfunction "A3_4") (pintype "unspecified"))
      (node (ref "U18") (pin "5") (pinfunction "A4_5") (pintype "unspecified"))
      (node (ref "U19") (pin "10") (pinfunction "GND_10") (pintype "unspecified"))
      (node (ref "U2") (pin "1") (pinfunction "GND_1") (pintype "unspecified"))
      (node (ref "U2") (pin "6") (pinfunction "THRES_6") (pintype "unspecified"))
      (node (ref "U20") (pin "8") (pinfunction "GND_8") (pintype "unspecified"))
      (node (ref "U21") (pin "8") (pinfunction "GND_8") (pintype "unspecified"))
      (node (ref "U22") (pin "7") (pinfunction "GND_7") (pintype "unspecified"))
      (node (ref "U23") (pin "7") (pinfunction "GND_7") (pintype "unspecified"))
      (node (ref "U3") (pin "7") (pinfunction "GND_7") (pintype "unspecified"))
      (node (ref "U4") (pin "7") (pinfunction "GND_7") (pintype "unspecified"))
      (node (ref "U5") (pin "7") (pinfunction "GND_7") (pintype "unspecified"))
      (node (ref "U6") (pin "1") (pinfunction "GND_1") (pintype "unspecified"))
      (node (ref "U7") (pin "10") (pinfunction "GND_10") (pintype "unspecified"))
      (node (ref "U8") (pin "1") (pinfunction "M_1") (pintype "unspecified"))
      (node (ref "U8") (pin "2") (pinfunction "N_2") (pintype "unspecified"))
      (node (ref "U8") (pin "8") (pinfunction "GND_8") (pintype "unspecified"))
      (node (ref "U9") (pin "1") (pinfunction "M_1") (pintype "unspecified"))
      (node (ref "U9") (pin "2") (pinfunction "N_2") (pintype "unspecified"))
      (node (ref "U9") (pin "8") (pinfunction "GND_8") (pintype "unspecified"))
    )
    (net (code "19") (name "HALT") (class "Default")
      (node (ref "U3") (pin "9") (pinfunction "4A_9") (pintype "unspecified"))
    )
    (net (code "20") (name "I0") (class "Default")
      (node (ref "U18") (pin "19") (pinfunction "#OE_19") (pintype "unspecified"))
    )
    (net (code "21") (name "I1") (class "Default")
      (node (ref "U16") (pin "10") (pinfunction "G2i_10") (pintype "unspecified"))
      (node (ref "U16") (pin "9") (pinfunction "G1i_9") (pintype "unspecified"))
      (node (ref "U17") (pin "10") (pinfunction "G2i_10") (pintype "unspecified"))
      (node (ref "U17") (pin "9") (pinfunction "G1i_9") (pintype "unspecified"))
    )
    (net (code "22") (name "JC_Load") (class "Default")
      (node (ref "U15") (pin "2") (pinfunction "1B_2") (pintype "unspecified"))
    )
    (net (code "23") (name "J_Load") (class "Default")
      (node (ref "U15") (pin "5") (pinfunction "2B_5") (pintype "unspecified"))
    )
    (net (code "24") (name "Log5") (class "Default")
      (node (ref "LED27") (pin "1") (pinfunction "A_1") (pintype "input"))
      (node (ref "U16") (pin "6") (pinfunction "4Q_6") (pintype "unspecified"))
    )
    (net (code "25") (name "Log6") (class "Default")
      (node (ref "LED26") (pin "1") (pinfunction "A_1") (pintype "input"))
      (node (ref "U16") (pin "5") (pinfunction "3Q_5") (pintype "unspecified"))
    )
    (net (code "26") (name "Log7") (class "Default")
      (node (ref "LED25") (pin "1") (pinfunction "A_1") (pintype "input"))
      (node (ref "U16") (pin "4") (pinfunction "2Q_4") (pintype "unspecified"))
    )
    (net (code "27") (name "Log8") (class "Default")
      (node (ref "LED24") (pin "1") (pinfunction "A_1") (pintype "input"))
      (node (ref "U16") (pin "3") (pinfunction "1Q_3") (pintype "unspecified"))
    )
    (net (code "28") (name "NOTCLK") (class "Default")
      (node (ref "U3") (pin "12") (pinfunction "6Y_12") (pintype "unspecified"))
    )
    (net (code "29") (name "Net-(LED1-A)") (class "Default")
      (node (ref "LED1") (pin "1") (pinfunction "A_1") (pintype "input"))
      (node (ref "U4") (pin "2") (pinfunction "1Y_2") (pintype "unspecified"))
      (node (ref "U6") (pin "3") (pinfunction "OUT_3") (pintype "unspecified"))
    )
    (net (code "30") (name "Net-(LED1-K)") (class "Default")
      (node (ref "LED1") (pin "2") (pinfunction "K_2") (pintype "input"))
      (node (ref "R4") (pin "1") (pinfunction "1_1") (pintype "input"))
    )
    (net (code "31") (name "Net-(LED2-A)") (class "Default")
      (node (ref "LED2") (pin "1") (pinfunction "A_1") (pintype "input"))
      (node (ref "U1") (pin "3") (pinfunction "OUT_3") (pintype "unspecified"))
      (node (ref "U4") (pin "5") (pinfunction "3A_5") (pintype "unspecified"))
    )
    (net (code "32") (name "Net-(LED2-K)") (class "Default")
      (node (ref "LED2") (pin "2") (pinfunction "K_2") (pintype "input"))
      (node (ref "R7") (pin "2") (pinfunction "2_2") (pintype "input"))
    )
    (net (code "33") (name "Net-(LED3-K)") (class "Default")
      (node (ref "LED3") (pin "2") (pinfunction "K_2") (pintype "input"))
      (node (ref "R8") (pin "1") (pinfunction "1_1") (pintype "input"))
    )
    (net (code "34") (name "Net-(LED4-K)") (class "Default")
      (node (ref "LED4") (pin "2") (pinfunction "K_2") (pintype "input"))
      (node (ref "R10") (pin "2") (pinfunction "2_2") (pintype "unspecified"))
    )
    (net (code "35") (name "Net-(LED5-K)") (class "Default")
      (node (ref "LED5") (pin "2") (pinfunction "K_2") (pintype "input"))
      (node (ref "R11") (pin "2") (pinfunction "2_2") (pintype "unspecified"))
    )
    (net (code "36") (name "Net-(LED6-K)") (class "Default")
      (node (ref "LED6") (pin "2") (pinfunction "K_2") (pintype "input"))
      (node (ref "R12") (pin "2") (pinfunction "2_2") (pintype "unspecified"))
    )
    (net (code "37") (name "Net-(LED7-K)") (class "Default")
      (node (ref "LED7") (pin "2") (pinfunction "K_2") (pintype "input"))
      (node (ref "R13") (pin "2") (pinfunction "2_2") (pintype "unspecified"))
    )
    (net (code "38") (name "Net-(LED8-K)") (class "Default")
      (node (ref "LED8") (pin "2") (pinfunction "K_2") (pintype "input"))
      (node (ref "R14") (pin "2") (pinfunction "2_2") (pintype "unspecified"))
    )
    (net (code "39") (name "Net-(LED9-K)") (class "Default")
      (node (ref "LED9") (pin "2") (pinfunction "K_2") (pintype "input"))
      (node (ref "R15") (pin "2") (pinfunction "2_2") (pintype "unspecified"))
    )
    (net (code "40") (name "Net-(LED10-K)") (class "Default")
      (node (ref "LED10") (pin "2") (pinfunction "K_2") (pintype "input"))
      (node (ref "R16") (pin "2") (pinfunction "2_2") (pintype "unspecified"))
    )
    (net (code "41") (name "Net-(LED11-K)") (class "Default")
      (node (ref "LED11") (pin "2") (pinfunction "K_2") (pintype "input"))
      (node (ref "R17") (pin "2") (pinfunction "2_2") (pintype "unspecified"))
    )
    (net (code "42") (name "Net-(LED12-K)") (class "Default")
      (node (ref "LED12") (pin "2") (pinfunction "K_2") (pintype "input"))
      (node (ref "R18") (pin "2") (pinfunction "2_2") (pintype "unspecified"))
    )
    (net (code "43") (name "Net-(LED13-K)") (class "Default")
      (node (ref "LED13") (pin "2") (pinfunction "K_2") (pintype "input"))
      (node (ref "R19") (pin "2") (pinfunction "2_2") (pintype "unspecified"))
    )
    (net (code "44") (name "Net-(LED14-K)") (class "Default")
      (node (ref "LED14") (pin "2") (pinfunction "K_2") (pintype "input"))
      (node (ref "R20") (pin "2") (pinfunction "2_2") (pintype "unspecified"))
    )
    (net (code "45") (name "Net-(LED15-K)") (class "Default")
      (node (ref "LED15") (pin "2") (pinfunction "K_2") (pintype "input"))
      (node (ref "R21") (pin "2") (pinfunction "2_2") (pintype "unspecified"))
    )
    (net (code "46") (name "Net-(LED16-K)") (class "Default")
      (node (ref "LED16") (pin "2") (pinfunction "K_2") (pintype "input"))
      (node (ref "R22") (pin "2") (pinfunction "2_2") (pintype "unspecified"))
    )
    (net (code "47") (name "Net-(LED17-K)") (class "Default")
      (node (ref "LED17") (pin "2") (pinfunction "K_2") (pintype "input"))
      (node (ref "R23") (pin "2") (pinfunction "2_2") (pintype "unspecified"))
    )
    (net (code "48") (name "Net-(LED18-K)") (class "Default")
      (node (ref "LED18") (pin "2") (pinfunction "K_2") (pintype "input"))
      (node (ref "R24") (pin "2") (pinfunction "2_2") (pintype "unspecified"))
    )
    (net (code "49") (name "Net-(LED19-K)") (class "Default")
      (node (ref "LED19") (pin "2") (pinfunction "K_2") (pintype "input"))
      (node (ref "R25") (pin "2") (pinfunction "2_2") (pintype "unspecified"))
    )
    (net (code "50") (name "Net-(LED20-A)") (class "Default")
      (node (ref "LED20") (pin "1") (pinfunction "A_1") (pintype "input"))
      (node (ref "U13") (pin "11") (pinfunction "B8_11") (pintype "unspecified"))
      (node (ref "U14") (pin "14") (pinfunction "QA_14") (pintype "unspecified"))
    )
    (net (code "51") (name "Net-(LED20-K)") (class "Default")
      (node (ref "LED20") (pin "2") (pinfunction "K_2") (pintype "input"))
      (node (ref "R26") (pin "1") (pinfunction "1_1") (pintype "unspecified"))
    )
    (net (code "52") (name "Net-(LED21-A)") (class "Default")
      (node (ref "LED21") (pin "1") (pinfunction "A_1") (pintype "input"))
      (node (ref "U13") (pin "12") (pinfunction "B7_12") (pintype "unspecified"))
      (node (ref "U14") (pin "13") (pinfunction "QB_13") (pintype "unspecified"))
    )
    (net (code "53") (name "Net-(LED21-K)") (class "Default")
      (node (ref "LED21") (pin "2") (pinfunction "K_2") (pintype "input"))
      (node (ref "R27") (pin "1") (pinfunction "1_1") (pintype "unspecified"))
    )
    (net (code "54") (name "Net-(LED22-A)") (class "Default")
      (node (ref "LED22") (pin "1") (pinfunction "A_1") (pintype "input"))
      (node (ref "U13") (pin "13") (pinfunction "B6_13") (pintype "unspecified"))
      (node (ref "U14") (pin "12") (pinfunction "QC_12") (pintype "unspecified"))
    )
    (net (code "55") (name "Net-(LED22-K)") (class "Default")
      (node (ref "LED22") (pin "2") (pinfunction "K_2") (pintype "input"))
      (node (ref "R28") (pin "1") (pinfunction "1_1") (pintype "unspecified"))
    )
    (net (code "56") (name "Net-(LED23-A)") (class "Default")
      (node (ref "LED23") (pin "1") (pinfunction "A_1") (pintype "input"))
      (node (ref "U13") (pin "14") (pinfunction "B5_14") (pintype "unspecified"))
      (node (ref "U14") (pin "11") (pinfunction "QD_11") (pintype "unspecified"))
    )
    (net (code "57") (name "Net-(LED23-K)") (class "Default")
      (node (ref "LED23") (pin "2") (pinfunction "K_2") (pintype "input"))
      (node (ref "R29") (pin "1") (pinfunction "1_1") (pintype "unspecified"))
    )
    (net (code "58") (name "Net-(LED24-K)") (class "Default")
      (node (ref "LED24") (pin "2") (pinfunction "K_2") (pintype "input"))
      (node (ref "R30") (pin "2") (pinfunction "2_2") (pintype "unspecified"))
    )
    (net (code "59") (name "Net-(LED25-K)") (class "Default")
      (node (ref "LED25") (pin "2") (pinfunction "K_2") (pintype "input"))
      (node (ref "R31") (pin "2") (pinfunction "2_2") (pintype "unspecified"))
    )
    (net (code "60") (name "Net-(LED26-K)") (class "Default")
      (node (ref "LED26") (pin "2") (pinfunction "K_2") (pintype "input"))
      (node (ref "R32") (pin "2") (pinfunction "2_2") (pintype "unspecified"))
    )
    (net (code "61") (name "Net-(LED27-K)") (class "Default")
      (node (ref "LED27") (pin "2") (pinfunction "K_2") (pintype "input"))
      (node (ref "R33") (pin "2") (pinfunction "2_2") (pintype "unspecified"))
    )
    (net (code "62") (name "Net-(LED28-A)") (class "Default")
      (node (ref "LED28") (pin "1") (pinfunction "A_1") (pintype "input"))
      (node (ref "U17") (pin "3") (pinfunction "1Q_3") (pintype "unspecified"))
      (node (ref "U18") (pin "6") (pinfunction "A5_6") (pintype "unspecified"))
    )
    (net (code "63") (name "Net-(LED28-K)") (class "Default")
      (node (ref "LED28") (pin "2") (pinfunction "K_2") (pintype "input"))
      (node (ref "R34") (pin "2") (pinfunction "2_2") (pintype "unspecified"))
    )
    (net (code "64") (name "Net-(LED29-A)") (class "Default")
      (node (ref "LED29") (pin "1") (pinfunction "A_1") (pintype "input"))
      (node (ref "U17") (pin "4") (pinfunction "2Q_4") (pintype "unspecified"))
      (node (ref "U18") (pin "7") (pinfunction "A6_7") (pintype "unspecified"))
    )
    (net (code "65") (name "Net-(LED29-K)") (class "Default")
      (node (ref "LED29") (pin "2") (pinfunction "K_2") (pintype "input"))
      (node (ref "R35") (pin "2") (pinfunction "2_2") (pintype "unspecified"))
    )
    (net (code "66") (name "Net-(LED30-A)") (class "Default")
      (node (ref "LED30") (pin "1") (pinfunction "A_1") (pintype "input"))
      (node (ref "U17") (pin "5") (pinfunction "3Q_5") (pintype "unspecified"))
      (node (ref "U18") (pin "8") (pinfunction "A7_8") (pintype "unspecified"))
    )
    (net (code "67") (name "Net-(LED30-K)") (class "Default")
      (node (ref "LED30") (pin "2") (pinfunction "K_2") (pintype "input"))
      (node (ref "R36") (pin "2") (pinfunction "2_2") (pintype "unspecified"))
    )
    (net (code "68") (name "Net-(LED31-A)") (class "Default")
      (node (ref "LED31") (pin "1") (pinfunction "A_1") (pintype "input"))
      (node (ref "U17") (pin "6") (pinfunction "4Q_6") (pintype "unspecified"))
      (node (ref "U18") (pin "9") (pinfunction "A8_9") (pintype "unspecified"))
    )
    (net (code "69") (name "Net-(LED31-K)") (class "Default")
      (node (ref "LED31") (pin "2") (pinfunction "K_2") (pintype "input"))
      (node (ref "R37") (pin "2") (pinfunction "2_2") (pintype "unspecified"))
    )
    (net (code "70") (name "Net-(LED32-A)") (class "Default")
      (node (ref "LED32") (pin "1") (pinfunction "A_1") (pintype "input"))
      (node (ref "U19") (pin "2") (pinfunction "A1_2") (pintype "unspecified"))
      (node (ref "U21") (pin "10") (pinfunction "S4_10") (pintype "unspecified"))
    )
    (net (code "71") (name "Net-(LED32-K)") (class "Default")
      (node (ref "LED32") (pin "2") (pinfunction "K_2") (pintype "input"))
      (node (ref "R38") (pin "2") (pinfunction "2_2") (pintype "unspecified"))
    )
    (net (code "72") (name "Net-(LED33-A)") (class "Default")
      (node (ref "LED33") (pin "1") (pinfunction "A_1") (pintype "input"))
      (node (ref "U19") (pin "3") (pinfunction "A2_3") (pintype "unspecified"))
      (node (ref "U21") (pin "13") (pinfunction "S3_13") (pintype "unspecified"))
    )
    (net (code "73") (name "Net-(LED33-K)") (class "Default")
      (node (ref "LED33") (pin "2") (pinfunction "K_2") (pintype "input"))
      (node (ref "R39") (pin "2") (pinfunction "2_2") (pintype "unspecified"))
    )
    (net (code "74") (name "Net-(LED34-A)") (class "Default")
      (node (ref "LED34") (pin "1") (pinfunction "A_1") (pintype "input"))
      (node (ref "U19") (pin "4") (pinfunction "A3_4") (pintype "unspecified"))
      (node (ref "U21") (pin "1") (pinfunction "S2_1") (pintype "unspecified"))
    )
    (net (code "75") (name "Net-(LED34-K)") (class "Default")
      (node (ref "LED34") (pin "2") (pinfunction "K_2") (pintype "input"))
      (node (ref "R40") (pin "2") (pinfunction "2_2") (pintype "unspecified"))
    )
    (net (code "76") (name "Net-(LED35-A)") (class "Default")
      (node (ref "LED35") (pin "1") (pinfunction "A_1") (pintype "input"))
      (node (ref "U19") (pin "5") (pinfunction "A4_5") (pintype "unspecified"))
      (node (ref "U21") (pin "4") (pinfunction "S1_4") (pintype "unspecified"))
    )
    (net (code "77") (name "Net-(LED35-K)") (class "Default")
      (node (ref "LED35") (pin "2") (pinfunction "K_2") (pintype "input"))
      (node (ref "R41") (pin "2") (pinfunction "2_2") (pintype "unspecified"))
    )
    (net (code "78") (name "Net-(LED36-A)") (class "Default")
      (node (ref "LED36") (pin "1") (pinfunction "A_1") (pintype "input"))
      (node (ref "U19") (pin "6") (pinfunction "A5_6") (pintype "unspecified"))
      (node (ref "U20") (pin "10") (pinfunction "S4_10") (pintype "unspecified"))
    )
    (net (code "79") (name "Net-(LED36-K)") (class "Default")
      (node (ref "LED36") (pin "2") (pinfunction "K_2") (pintype "input"))
      (node (ref "R42") (pin "2") (pinfunction "2_2") (pintype "unspecified"))
    )
    (net (code "80") (name "Net-(LED37-A)") (class "Default")
      (node (ref "LED37") (pin "1") (pinfunction "A_1") (pintype "input"))
      (node (ref "U19") (pin "7") (pinfunction "A6_7") (pintype "unspecified"))
      (node (ref "U20") (pin "13") (pinfunction "S3_13") (pintype "unspecified"))
    )
    (net (code "81") (name "Net-(LED37-K)") (class "Default")
      (node (ref "LED37") (pin "2") (pinfunction "K_2") (pintype "input"))
      (node (ref "R43") (pin "2") (pinfunction "2_2") (pintype "unspecified"))
    )
    (net (code "82") (name "Net-(LED38-A)") (class "Default")
      (node (ref "LED38") (pin "1") (pinfunction "A_1") (pintype "input"))
      (node (ref "U19") (pin "8") (pinfunction "A7_8") (pintype "unspecified"))
      (node (ref "U20") (pin "1") (pinfunction "S2_1") (pintype "unspecified"))
    )
    (net (code "83") (name "Net-(LED38-K)") (class "Default")
      (node (ref "LED38") (pin "2") (pinfunction "K_2") (pintype "input"))
      (node (ref "R44") (pin "2") (pinfunction "2_2") (pintype "unspecified"))
    )
    (net (code "84") (name "Net-(LED39-A)") (class "Default")
      (node (ref "LED39") (pin "1") (pinfunction "A_1") (pintype "input"))
      (node (ref "U19") (pin "9") (pinfunction "A8_9") (pintype "unspecified"))
      (node (ref "U20") (pin "4") (pinfunction "S1_4") (pintype "unspecified"))
    )
    (net (code "85") (name "Net-(LED39-K)") (class "Default")
      (node (ref "LED39") (pin "2") (pinfunction "K_2") (pintype "input"))
      (node (ref "R45") (pin "2") (pinfunction "2_2") (pintype "unspecified"))
    )
    (net (code "86") (name "Net-(LED40-K)") (class "Default")
      (node (ref "LED40") (pin "2") (pinfunction "K_2") (pintype "input"))
      (node (ref "R46") (pin "1") (pinfunction "1_1") (pintype "unspecified"))
    )
    (net (code "87") (name "Net-(LED41-K)") (class "Default")
      (node (ref "LED41") (pin "2") (pinfunction "K_2") (pintype "input"))
      (node (ref "R47") (pin "1") (pinfunction "1_1") (pintype "unspecified"))
    )
    (net (code "88") (name "Net-(LED42-K)") (class "Default")
      (node (ref "LED42") (pin "2") (pinfunction "K_2") (pintype "input"))
      (node (ref "R48") (pin "1") (pinfunction "1_1") (pintype "unspecified"))
    )
    (net (code "89") (name "Net-(LED43-K)") (class "Default")
      (node (ref "LED43") (pin "2") (pinfunction "K_2") (pintype "input"))
      (node (ref "R49") (pin "1") (pinfunction "1_1") (pintype "unspecified"))
    )
    (net (code "90") (name "Net-(LED44-K)") (class "Default")
      (node (ref "LED44") (pin "2") (pinfunction "K_2") (pintype "input"))
      (node (ref "R50") (pin "1") (pinfunction "1_1") (pintype "unspecified"))
    )
    (net (code "91") (name "Net-(LED45-K)") (class "Default")
      (node (ref "LED45") (pin "2") (pinfunction "K_2") (pintype "input"))
      (node (ref "R51") (pin "1") (pinfunction "1_1") (pintype "unspecified"))
    )
    (net (code "92") (name "Net-(LED46-K)") (class "Default")
      (node (ref "LED46") (pin "2") (pinfunction "K_2") (pintype "input"))
      (node (ref "R52") (pin "1") (pinfunction "1_1") (pintype "unspecified"))
    )
    (net (code "93") (name "Net-(LED47-K)") (class "Default")
      (node (ref "LED47") (pin "2") (pinfunction "K_2") (pintype "input"))
      (node (ref "R53") (pin "1") (pinfunction "1_1") (pintype "unspecified"))
    )
    (net (code "94") (name "Net-(R3-Pad2)") (class "Default")
      (node (ref "R3") (pin "2") (pinfunction "2_2") (pintype "input"))
      (node (ref "VR12") (pin "3") (pinfunction "3_3") (pintype "input"))
    )
    (net (code "95") (name "Net-(U1-CONT)") (class "Default")
      (node (ref "C5") (pin "2") (pinfunction "2_2") (pintype "unspecified"))
      (node (ref "U1") (pin "5") (pinfunction "CONT_5") (pintype "unspecified"))
    )
    (net (code "96") (name "Net-(U1-DISCH)") (class "Default")
      (node (ref "C4") (pin "2") (pinfunction "2_2") (pintype "unspecified"))
      (node (ref "R2") (pin "1") (pinfunction "1_1") (pintype "input"))
      (node (ref "U1") (pin "6") (pinfunction "THRES_6") (pintype "unspecified"))
      (node (ref "U1") (pin "7") (pinfunction "DISCH_7") (pintype "unspecified"))
    )
    (net (code "97") (name "Net-(U1-TRIG)") (class "Default")
      (node (ref "R5") (pin "2") (pinfunction "2_2") (pintype "input"))
      (node (ref "SW3") (pin "3") (pinfunction "3_3") (pintype "unspecified"))
      (node (ref "U1") (pin "2") (pinfunction "TRIG_2") (pintype "unspecified"))
    )
    (net (code "98") (name "Net-(U2-CONT)") (class "Default")
      (node (ref "C6") (pin "1") (pinfunction "1_1") (pintype "unspecified"))
      (node (ref "U2") (pin "5") (pinfunction "CONT_5") (pintype "unspecified"))
    )
    (net (code "99") (name "Net-(U2-OUT)") (class "Default")
      (node (ref "U2") (pin "3") (pinfunction "OUT_3") (pintype "unspecified"))
      (node (ref "U3") (pin "1") (pinfunction "1A_1") (pintype "unspecified"))
      (node (ref "U4") (pin "1") (pinfunction "1A_1") (pintype "unspecified"))
    )
    (net (code "100") (name "Net-(U2-RESET)") (class "Default")
      (node (ref "R6") (pin "2") (pinfunction "2_2") (pintype "input"))
      (node (ref "SW1") (pin "3") (pinfunction "3_3") (pintype "unspecified"))
      (node (ref "U2") (pin "4") (pinfunction "RESET_4") (pintype "unspecified"))
    )
    (net (code "101") (name "Net-(U2-TRIG)") (class "Default")
      (node (ref "R9") (pin "1") (pinfunction "1_1") (pintype "input"))
      (node (ref "SW1") (pin "1") (pinfunction "1_1") (pintype "unspecified"))
      (node (ref "U2") (pin "2") (pinfunction "TRIG_2") (pintype "unspecified"))
    )
    (net (code "102") (name "Net-(U3-1Y)") (class "Default")
      (node (ref "U3") (pin "2") (pinfunction "1Y_2") (pintype "unspecified"))
      (node (ref "U4") (pin "4") (pinfunction "2Y_4") (pintype "unspecified"))
    )
    (net (code "103") (name "Net-(U3-4Y)") (class "Default")
      (node (ref "U3") (pin "8") (pinfunction "4Y_8") (pintype "unspecified"))
      (node (ref "U4") (pin "10") (pinfunction "5Y_10") (pintype "unspecified"))
    )
    (net (code "104") (name "Net-(U4-2A)") (class "Default")
      (node (ref "U4") (pin "3") (pinfunction "2A_3") (pintype "unspecified"))
      (node (ref "U5") (pin "1") (pinfunction "1A_1") (pintype "unspecified"))
    )
    (net (code "105") (name "Net-(U4-3Y)") (class "Default")
      (node (ref "U4") (pin "6") (pinfunction "3Y_6") (pintype "unspecified"))
      (node (ref "U5") (pin "2") (pinfunction "1Y_2") (pintype "unspecified"))
    )
    (net (code "106") (name "Net-(U4-4A)") (class "Default")
      (node (ref "U4") (pin "9") (pinfunction "4A_9") (pintype "unspecified"))
      (node (ref "U5") (pin "3") (pinfunction "2A_3") (pintype "unspecified"))
    )
    (net (code "107") (name "Net-(U6-CONT)") (class "Default")
      (node (ref "C3") (pin "2") (pinfunction "2_2") (pintype "unspecified"))
      (node (ref "U6") (pin "5") (pinfunction "CONT_5") (pintype "unspecified"))
    )
    (net (code "108") (name "Net-(U6-DISCH)") (class "Default")
      (node (ref "R1") (pin "1") (pinfunction "1_1") (pintype "input"))
      (node (ref "R3") (pin "1") (pinfunction "1_1") (pintype "input"))
      (node (ref "U6") (pin "7") (pinfunction "DISCH_7") (pintype "unspecified"))
    )
    (net (code "109") (name "Net-(U6-THRES)") (class "Default")
      (node (ref "C7") (pin "1") (pinfunction "1_1") (pintype "unspecified"))
      (node (ref "U6") (pin "2") (pinfunction "TRIG_2") (pintype "unspecified"))
      (node (ref "U6") (pin "6") (pinfunction "THRES_6") (pintype "unspecified"))
      (node (ref "VR12") (pin "2") (pinfunction "2_2") (pintype "input"))
    )
    (net (code "110") (name "Net-(U14-Load)") (class "Default")
      (node (ref "U14") (pin "9") (pinfunction "Load_9") (pintype "unspecified"))
      (node (ref "U15") (pin "8") (pinfunction "3Y_8") (pintype "unspecified"))
    )
    (net (code "111") (name "Net-(U15-1Y)") (class "Default")
      (node (ref "U15") (pin "3") (pinfunction "1Y_3") (pintype "unspecified"))
      (node (ref "U15") (pin "4") (pinfunction "2A_4") (pintype "unspecified"))
    )
    (net (code "112") (name "Net-(U15-2Y)") (class "Default")
      (node (ref "U15") (pin "10") (pinfunction "3A_10") (pintype "unspecified"))
      (node (ref "U15") (pin "6") (pinfunction "2Y_6") (pintype "unspecified"))
      (node (ref "U15") (pin "9") (pinfunction "3B_9") (pintype "unspecified"))
    )
    (net (code "113") (name "Net-(U20-B1)") (class "Default")
      (node (ref "U20") (pin "6") (pinfunction "B1_6") (pintype "unspecified"))
      (node (ref "U23") (pin "6") (pinfunction "2Y_6") (pintype "unspecified"))
    )
    (net (code "114") (name "Net-(U20-B2)") (class "Default")
      (node (ref "U20") (pin "2") (pinfunction "B2_2") (pintype "unspecified"))
      (node (ref "U23") (pin "3") (pinfunction "1Y_3") (pintype "unspecified"))
    )
    (net (code "115") (name "Net-(U20-B3)") (class "Default")
      (node (ref "U20") (pin "15") (pinfunction "B3_15") (pintype "unspecified"))
      (node (ref "U23") (pin "11") (pinfunction "4Y_11") (pintype "unspecified"))
    )
    (net (code "116") (name "Net-(U20-B4)") (class "Default")
      (node (ref "U20") (pin "11") (pinfunction "B4_11") (pintype "unspecified"))
      (node (ref "U23") (pin "8") (pinfunction "3Y_8") (pintype "unspecified"))
    )
    (net (code "117") (name "Net-(U20-C4)") (class "Default")
      (node (ref "U20") (pin "9") (pinfunction "C4_9") (pintype "unspecified"))
      (node (ref "U21") (pin "7") (pinfunction "C0_7") (pintype "unspecified"))
    )
    (net (code "118") (name "Net-(U21-B1)") (class "Default")
      (node (ref "U21") (pin "6") (pinfunction "B1_6") (pintype "unspecified"))
      (node (ref "U22") (pin "6") (pinfunction "2Y_6") (pintype "unspecified"))
    )
    (net (code "119") (name "Net-(U21-B2)") (class "Default")
      (node (ref "U21") (pin "2") (pinfunction "B2_2") (pintype "unspecified"))
      (node (ref "U22") (pin "3") (pinfunction "1Y_3") (pintype "unspecified"))
    )
    (net (code "120") (name "Net-(U21-B3)") (class "Default")
      (node (ref "U21") (pin "15") (pinfunction "B3_15") (pintype "unspecified"))
      (node (ref "U22") (pin "11") (pinfunction "4Y_11") (pintype "unspecified"))
    )
    (net (code "121") (name "Net-(U21-B4)") (class "Default")
      (node (ref "U21") (pin "11") (pinfunction "B4_11") (pintype "unspecified"))
      (node (ref "U22") (pin "8") (pinfunction "3Y_8") (pintype "unspecified"))
    )
    (net (code "122") (name "REGA1") (class "Default")
      (node (ref "LED4") (pin "1") (pinfunction "A_1") (pintype "input"))
      (node (ref "U20") (pin "5") (pinfunction "A1_5") (pintype "unspecified"))
      (node (ref "U7") (pin "9") (pinfunction "A8_9") (pintype "unspecified"))
      (node (ref "U9") (pin "6") (pinfunction "4Q_6") (pintype "unspecified"))
    )
    (net (code "123") (name "REGA2") (class "Default")
      (node (ref "LED5") (pin "1") (pinfunction "A_1") (pintype "input"))
      (node (ref "U20") (pin "3") (pinfunction "A2_3") (pintype "unspecified"))
      (node (ref "U7") (pin "8") (pinfunction "A7_8") (pintype "unspecified"))
      (node (ref "U9") (pin "5") (pinfunction "3Q_5") (pintype "unspecified"))
    )
    (net (code "124") (name "REGA3") (class "Default")
      (node (ref "LED6") (pin "1") (pinfunction "A_1") (pintype "input"))
      (node (ref "U20") (pin "14") (pinfunction "A3_14") (pintype "unspecified"))
      (node (ref "U7") (pin "7") (pinfunction "A6_7") (pintype "unspecified"))
      (node (ref "U9") (pin "4") (pinfunction "2Q_4") (pintype "unspecified"))
    )
    (net (code "125") (name "REGA4") (class "Default")
      (node (ref "LED7") (pin "1") (pinfunction "A_1") (pintype "input"))
      (node (ref "U20") (pin "12") (pinfunction "A4_12") (pintype "unspecified"))
      (node (ref "U7") (pin "6") (pinfunction "A5_6") (pintype "unspecified"))
      (node (ref "U9") (pin "3") (pinfunction "1Q_3") (pintype "unspecified"))
    )
    (net (code "126") (name "REGA5") (class "Default")
      (node (ref "LED8") (pin "1") (pinfunction "A_1") (pintype "input"))
      (node (ref "U21") (pin "5") (pinfunction "A1_5") (pintype "unspecified"))
      (node (ref "U7") (pin "5") (pinfunction "A4_5") (pintype "unspecified"))
      (node (ref "U8") (pin "6") (pinfunction "4Q_6") (pintype "unspecified"))
    )
    (net (code "127") (name "REGA6") (class "Default")
      (node (ref "LED9") (pin "1") (pinfunction "A_1") (pintype "input"))
      (node (ref "U21") (pin "3") (pinfunction "A2_3") (pintype "unspecified"))
      (node (ref "U7") (pin "4") (pinfunction "A3_4") (pintype "unspecified"))
      (node (ref "U8") (pin "5") (pinfunction "3Q_5") (pintype "unspecified"))
    )
    (net (code "128") (name "REGA7") (class "Default")
      (node (ref "LED10") (pin "1") (pinfunction "A_1") (pintype "input"))
      (node (ref "U21") (pin "14") (pinfunction "A3_14") (pintype "unspecified"))
      (node (ref "U7") (pin "3") (pinfunction "A2_3") (pintype "unspecified"))
      (node (ref "U8") (pin "4") (pinfunction "2Q_4") (pintype "unspecified"))
    )
    (net (code "129") (name "REGA8") (class "Default")
      (node (ref "LED11") (pin "1") (pinfunction "A_1") (pintype "input"))
      (node (ref "U21") (pin "12") (pinfunction "A4_12") (pintype "unspecified"))
      (node (ref "U7") (pin "2") (pinfunction "A1_2") (pintype "unspecified"))
      (node (ref "U8") (pin "3") (pinfunction "1Q_3") (pintype "unspecified"))
    )
    (net (code "130") (name "REGB1") (class "Default")
      (node (ref "LED12") (pin "1") (pinfunction "A_1") (pintype "input"))
      (node (ref "U10") (pin "9") (pinfunction "A8_9") (pintype "unspecified"))
      (node (ref "U12") (pin "6") (pinfunction "4Q_6") (pintype "unspecified"))
      (node (ref "U23") (pin "4") (pinfunction "2A_4") (pintype "unspecified"))
    )
    (net (code "131") (name "REGB2") (class "Default")
      (node (ref "LED13") (pin "1") (pinfunction "A_1") (pintype "input"))
      (node (ref "U10") (pin "8") (pinfunction "A7_8") (pintype "unspecified"))
      (node (ref "U12") (pin "5") (pinfunction "3Q_5") (pintype "unspecified"))
      (node (ref "U23") (pin "1") (pinfunction "1A_1") (pintype "unspecified"))
    )
    (net (code "132") (name "REGB3") (class "Default")
      (node (ref "LED14") (pin "1") (pinfunction "A_1") (pintype "input"))
      (node (ref "U10") (pin "7") (pinfunction "A6_7") (pintype "unspecified"))
      (node (ref "U12") (pin "4") (pinfunction "2Q_4") (pintype "unspecified"))
      (node (ref "U23") (pin "12") (pinfunction "4A_12") (pintype "unspecified"))
    )
    (net (code "133") (name "REGB4") (class "Default")
      (node (ref "LED15") (pin "1") (pinfunction "A_1") (pintype "input"))
      (node (ref "U10") (pin "6") (pinfunction "A5_6") (pintype "unspecified"))
      (node (ref "U12") (pin "3") (pinfunction "1Q_3") (pintype "unspecified"))
      (node (ref "U23") (pin "9") (pinfunction "3A_9") (pintype "unspecified"))
    )
    (net (code "134") (name "REGB5") (class "Default")
      (node (ref "LED16") (pin "1") (pinfunction "A_1") (pintype "input"))
      (node (ref "U10") (pin "5") (pinfunction "A4_5") (pintype "unspecified"))
      (node (ref "U11") (pin "6") (pinfunction "4Q_6") (pintype "unspecified"))
      (node (ref "U22") (pin "4") (pinfunction "2A_4") (pintype "unspecified"))
    )
    (net (code "135") (name "REGB6") (class "Default")
      (node (ref "LED17") (pin "1") (pinfunction "A_1") (pintype "input"))
      (node (ref "U10") (pin "4") (pinfunction "A3_4") (pintype "unspecified"))
      (node (ref "U11") (pin "5") (pinfunction "3Q_5") (pintype "unspecified"))
      (node (ref "U22") (pin "1") (pinfunction "1A_1") (pintype "unspecified"))
    )
    (net (code "136") (name "REGB7") (class "Default")
      (node (ref "LED18") (pin "1") (pinfunction "A_1") (pintype "input"))
      (node (ref "U10") (pin "3") (pinfunction "A2_3") (pintype "unspecified"))
      (node (ref "U11") (pin "4") (pinfunction "2Q_4") (pintype "unspecified"))
      (node (ref "U22") (pin "12") (pinfunction "4A_12") (pintype "unspecified"))
    )
    (net (code "137") (name "REGB8") (class "Default")
      (node (ref "LED19") (pin "1") (pinfunction "A_1") (pintype "input"))
      (node (ref "U10") (pin "2") (pinfunction "A1_2") (pintype "unspecified"))
      (node (ref "U11") (pin "3") (pinfunction "1Q_3") (pintype "unspecified"))
      (node (ref "U22") (pin "9") (pinfunction "3A_9") (pintype "unspecified"))
    )
    (net (code "138") (name "SUB") (class "Default")
      (node (ref "U20") (pin "7") (pinfunction "C0_7") (pintype "unspecified"))
      (node (ref "U22") (pin "10") (pinfunction "3B_10") (pintype "unspecified"))
      (node (ref "U22") (pin "13") (pinfunction "4B_13") (pintype "unspecified"))
      (node (ref "U22") (pin "2") (pinfunction "1B_2") (pintype "unspecified"))
      (node (ref "U22") (pin "5") (pinfunction "2B_5") (pintype "unspecified"))
      (node (ref "U23") (pin "10") (pinfunction "3B_10") (pintype "unspecified"))
      (node (ref "U23") (pin "13") (pinfunction "4B_13") (pintype "unspecified"))
      (node (ref "U23") (pin "2") (pinfunction "1B_2") (pintype "unspecified"))
      (node (ref "U23") (pin "5") (pinfunction "2B_5") (pintype "unspecified"))
    )
    (net (code "139") (name "VCC") (class "Default")
      (node (ref "C1") (pin "2") (pinfunction "2_2") (pintype "unspecified"))
      (node (ref "R1") (pin "2") (pinfunction "2_2") (pintype "input"))
      (node (ref "R2") (pin "2") (pinfunction "2_2") (pintype "input"))
      (node (ref "R5") (pin "1") (pinfunction "1_1") (pintype "input"))
      (node (ref "R6") (pin "1") (pinfunction "1_1") (pintype "input"))
      (node (ref "R9") (pin "2") (pinfunction "2_2") (pintype "input"))
      (node (ref "U1") (pin "4") (pinfunction "RESET_4") (pintype "unspecified"))
      (node (ref "U1") (pin "8") (pinfunction "VCC_8") (pintype "unspecified"))
      (node (ref "U10") (pin "1") (pinfunction "DIR_1") (pintype "unspecified"))
      (node (ref "U10") (pin "20") (pinfunction "VCC_20") (pintype "unspecified"))
      (node (ref "U11") (pin "16") (pinfunction "VCC_16") (pintype "unspecified"))
      (node (ref "U12") (pin "16") (pinfunction "VCC_16") (pintype "unspecified"))
      (node (ref "U13") (pin "20") (pinfunction "VCC_20") (pintype "unspecified"))
      (node (ref "U14") (pin "16") (pinfunction "VCC_16") (pintype "unspecified"))
      (node (ref "U15") (pin "14") (pinfunction "VCC_14") (pintype "unspecified"))
      (node (ref "U16") (pin "16") (pinfunction "VCC_16") (pintype "unspecified"))
      (node (ref "U17") (pin "16") (pinfunction "VCC_16") (pintype "unspecified"))
      (node (ref "U18") (pin "1") (pinfunction "DIR_1") (pintype "unspecified"))
      (node (ref "U18") (pin "20") (pinfunction "VCC_20") (pintype "unspecified"))
      (node (ref "U19") (pin "1") (pinfunction "DIR_1") (pintype "unspecified"))
      (node (ref "U19") (pin "20") (pinfunction "VCC_20") (pintype "unspecified"))
      (node (ref "U2") (pin "8") (pinfunction "VCC_8") (pintype "unspecified"))
      (node (ref "U20") (pin "16") (pinfunction "VCC_16") (pintype "unspecified"))
      (node (ref "U21") (pin "16") (pinfunction "VCC_16") (pintype "unspecified"))
      (node (ref "U22") (pin "14") (pinfunction "VCC_14") (pintype "unspecified"))
      (node (ref "U23") (pin "14") (pinfunction "VCC_14") (pintype "unspecified"))
      (node (ref "U3") (pin "14") (pinfunction "VCC_14") (pintype "unspecified"))
      (node (ref "U4") (pin "14") (pinfunction "VCC_14") (pintype "unspecified"))
      (node (ref "U5") (pin "14") (pinfunction "VCC_14") (pintype "unspecified"))
      (node (ref "U6") (pin "4") (pinfunction "RESET_4") (pintype "unspecified"))
      (node (ref "U6") (pin "8") (pinfunction "VCC_8") (pintype "unspecified"))
      (node (ref "U7") (pin "1") (pinfunction "DIR_1") (pintype "unspecified"))
      (node (ref "U7") (pin "20") (pinfunction "VCC_20") (pintype "unspecified"))
      (node (ref "U8") (pin "16") (pinfunction "VCC_16") (pintype "unspecified"))
      (node (ref "U9") (pin "16") (pinfunction "VCC_16") (pintype "unspecified"))
    )
    (net (code "140") (name "unconnected-(SW1-Pad4)") (class "Default")
      (node (ref "SW1") (pin "4") (pinfunction "4_4") (pintype "unspecified+no_connect"))
    )
    (net (code "141") (name "unconnected-(SW1-Pad5)") (class "Default")
      (node (ref "SW1") (pin "5") (pinfunction "5_5") (pintype "unspecified+no_connect"))
    )
    (net (code "142") (name "unconnected-(SW1-Pad6)") (class "Default")
      (node (ref "SW1") (pin "6") (pinfunction "6_6") (pintype "unspecified+no_connect"))
    )
    (net (code "143") (name "unconnected-(SW3-Pad2)") (class "Default")
      (node (ref "SW3") (pin "2") (pinfunction "2_2") (pintype "unspecified+no_connect"))
    )
    (net (code "144") (name "unconnected-(SW3-Pad4)") (class "Default")
      (node (ref "SW3") (pin "4") (pinfunction "4_4") (pintype "unspecified+no_connect"))
    )
    (net (code "145") (name "unconnected-(U2-DISCH-Pad7)") (class "Default")
      (node (ref "U2") (pin "7") (pinfunction "DISCH_7") (pintype "unspecified+no_connect"))
    )
    (net (code "146") (name "unconnected-(U3-2A-Pad3)") (class "Default")
      (node (ref "U3") (pin "3") (pinfunction "2A_3") (pintype "unspecified+no_connect"))
    )
    (net (code "147") (name "unconnected-(U3-2Y-Pad4)") (class "Default")
      (node (ref "U3") (pin "4") (pinfunction "2Y_4") (pintype "unspecified+no_connect"))
    )
    (net (code "148") (name "unconnected-(U3-3A-Pad5)") (class "Default")
      (node (ref "U3") (pin "5") (pinfunction "3A_5") (pintype "unspecified+no_connect"))
    )
    (net (code "149") (name "unconnected-(U3-3Y-Pad6)") (class "Default")
      (node (ref "U3") (pin "6") (pinfunction "3Y_6") (pintype "unspecified+no_connect"))
    )
    (net (code "150") (name "unconnected-(U3-5A-Pad11)") (class "Default")
      (node (ref "U3") (pin "11") (pinfunction "5A_11") (pintype "unspecified+no_connect"))
    )
    (net (code "151") (name "unconnected-(U3-5Y-Pad10)") (class "Default")
      (node (ref "U3") (pin "10") (pinfunction "5Y_10") (pintype "unspecified+no_connect"))
    )
    (net (code "152") (name "unconnected-(U4-5A-Pad11)") (class "Default")
      (node (ref "U4") (pin "11") (pinfunction "5A_11") (pintype "unspecified+no_connect"))
    )
    (net (code "153") (name "unconnected-(U4-6A-Pad13)") (class "Default")
      (node (ref "U4") (pin "13") (pinfunction "6A_13") (pintype "unspecified+no_connect"))
    )
    (net (code "154") (name "unconnected-(U4-6Y-Pad12)") (class "Default")
      (node (ref "U4") (pin "12") (pinfunction "6Y_12") (pintype "unspecified+no_connect"))
    )
    (net (code "155") (name "unconnected-(U5-2Y-Pad4)") (class "Default")
      (node (ref "U5") (pin "4") (pinfunction "2Y_4") (pintype "unspecified+no_connect"))
    )
    (net (code "156") (name "unconnected-(U5-3A-Pad5)") (class "Default")
      (node (ref "U5") (pin "5") (pinfunction "3A_5") (pintype "unspecified+no_connect"))
    )
    (net (code "157") (name "unconnected-(U5-3Y-Pad6)") (class "Default")
      (node (ref "U5") (pin "6") (pinfunction "3Y_6") (pintype "unspecified+no_connect"))
    )
    (net (code "158") (name "unconnected-(U5-4A-Pad9)") (class "Default")
      (node (ref "U5") (pin "9") (pinfunction "4A_9") (pintype "unspecified+no_connect"))
    )
    (net (code "159") (name "unconnected-(U5-4Y-Pad8)") (class "Default")
      (node (ref "U5") (pin "8") (pinfunction "4Y_8") (pintype "unspecified+no_connect"))
    )
    (net (code "160") (name "unconnected-(U5-5A-Pad11)") (class "Default")
      (node (ref "U5") (pin "11") (pinfunction "5A_11") (pintype "unspecified+no_connect"))
    )
    (net (code "161") (name "unconnected-(U5-5Y-Pad10)") (class "Default")
      (node (ref "U5") (pin "10") (pinfunction "5Y_10") (pintype "unspecified+no_connect"))
    )
    (net (code "162") (name "unconnected-(U5-6A-Pad13)") (class "Default")
      (node (ref "U5") (pin "13") (pinfunction "6A_13") (pintype "unspecified+no_connect"))
    )
    (net (code "163") (name "unconnected-(U5-6Y-Pad12)") (class "Default")
      (node (ref "U5") (pin "12") (pinfunction "6Y_12") (pintype "unspecified+no_connect"))
    )
    (net (code "164") (name "unconnected-(U14-Ripple_Carry_Output-Pad15)") (class "Default")
      (node (ref "U14") (pin "15") (pinfunction "Ripple_Carry_Output_15") (pintype "unspecified+no_connect"))
    )
    (net (code "165") (name "unconnected-(U15-4A-Pad13)") (class "Default")
      (node (ref "U15") (pin "13") (pinfunction "4A_13") (pintype "unspecified+no_connect"))
    )
    (net (code "166") (name "unconnected-(U15-4B-Pad12)") (class "Default")
      (node (ref "U15") (pin "12") (pinfunction "4B_12") (pintype "unspecified+no_connect"))
    )
    (net (code "167") (name "unconnected-(U15-4Y-Pad11)") (class "Default")
      (node (ref "U15") (pin "11") (pinfunction "4Y_11") (pintype "unspecified+no_connect"))
    )
    (net (code "168") (name "unconnected-(VR12-Pad1)") (class "Default")
      (node (ref "VR12") (pin "1") (pinfunction "1_1") (pintype "input+no_connect"))
    )
  )
)
